# schematic.net
KiCad netlist of a schematic drawn in EAGLE
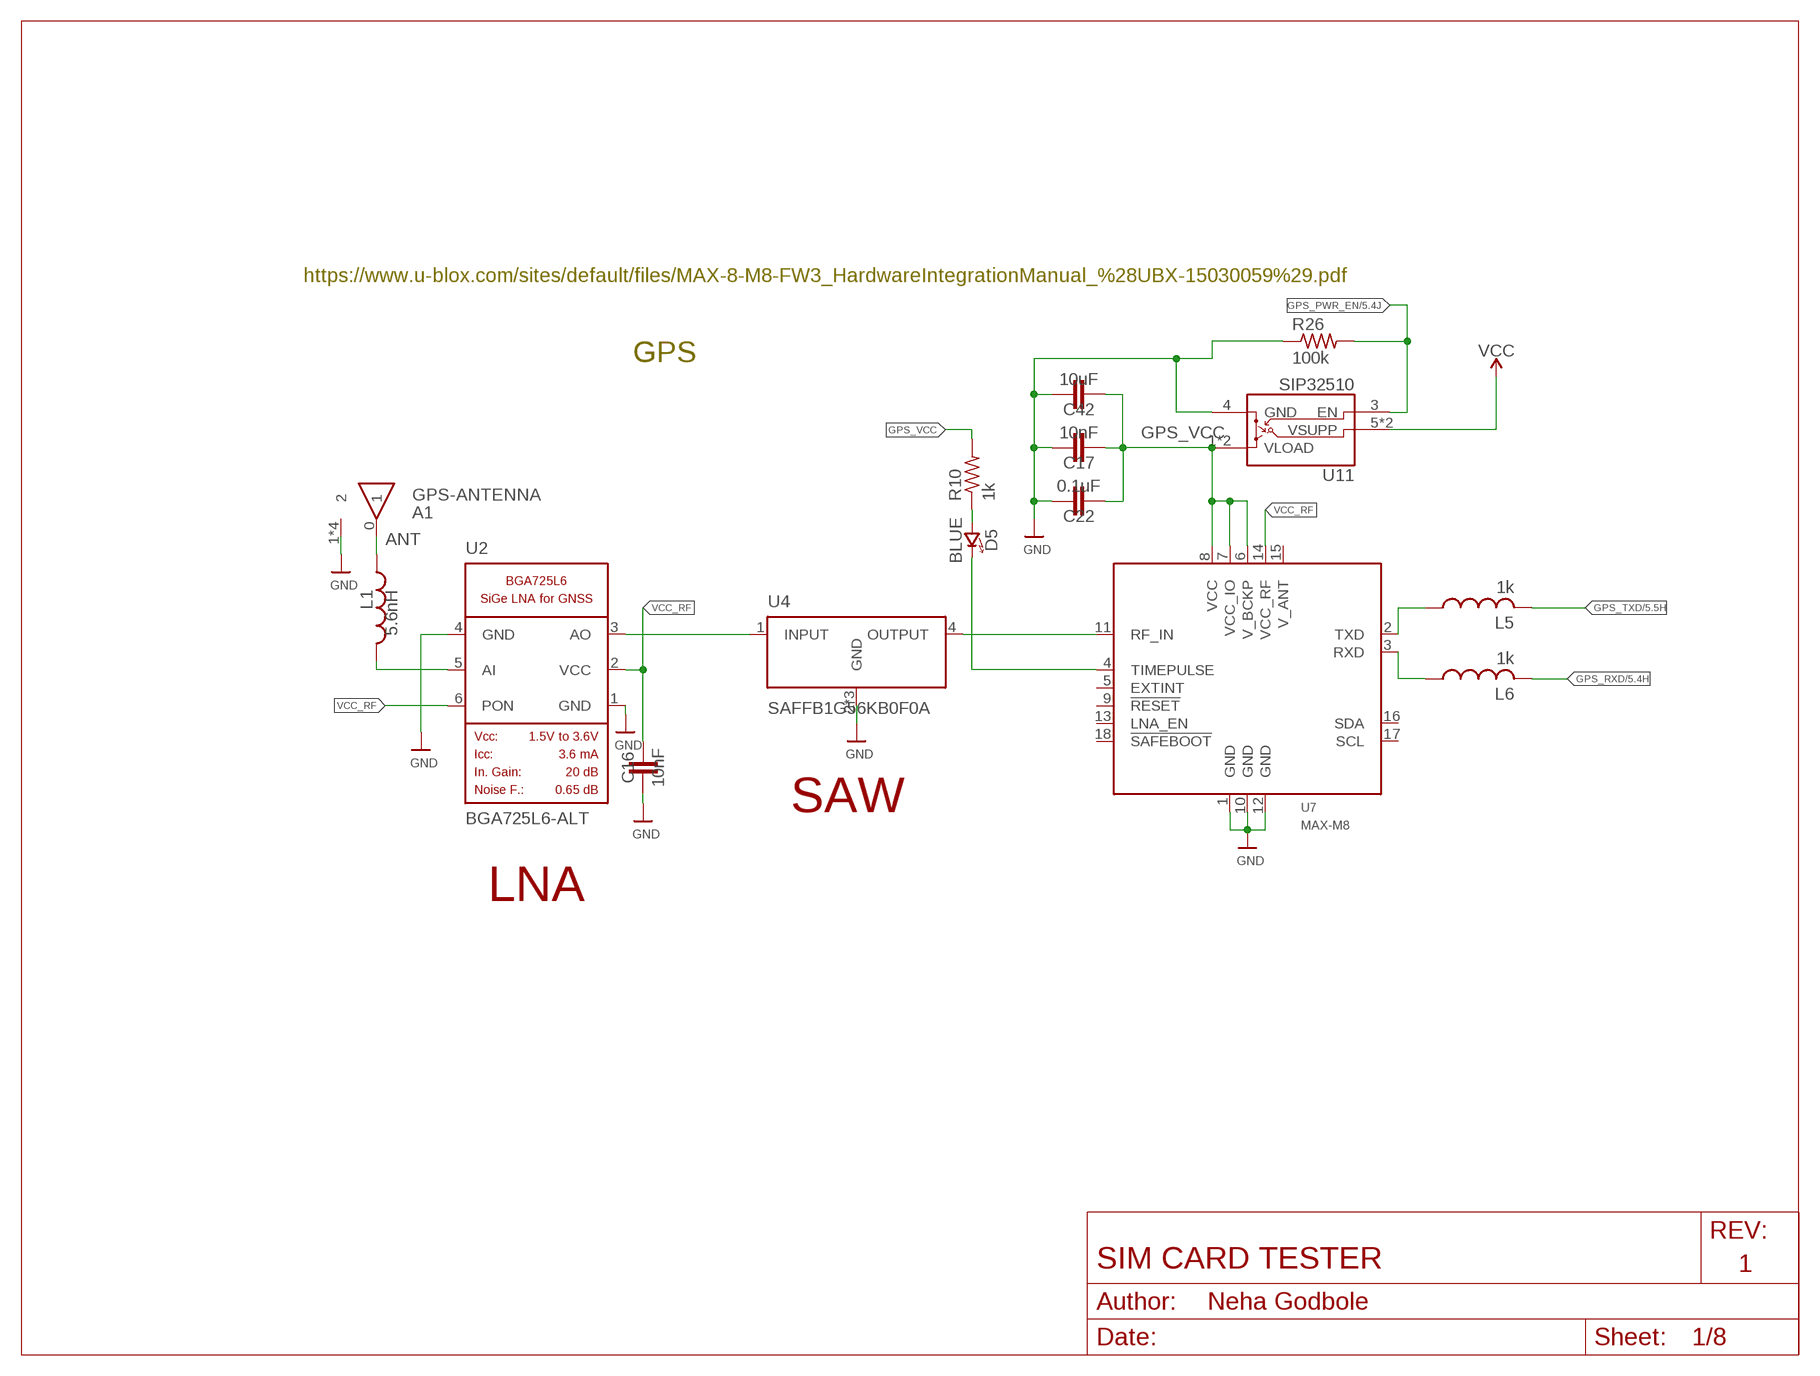
[diagram p0: schematic, sheet 1]
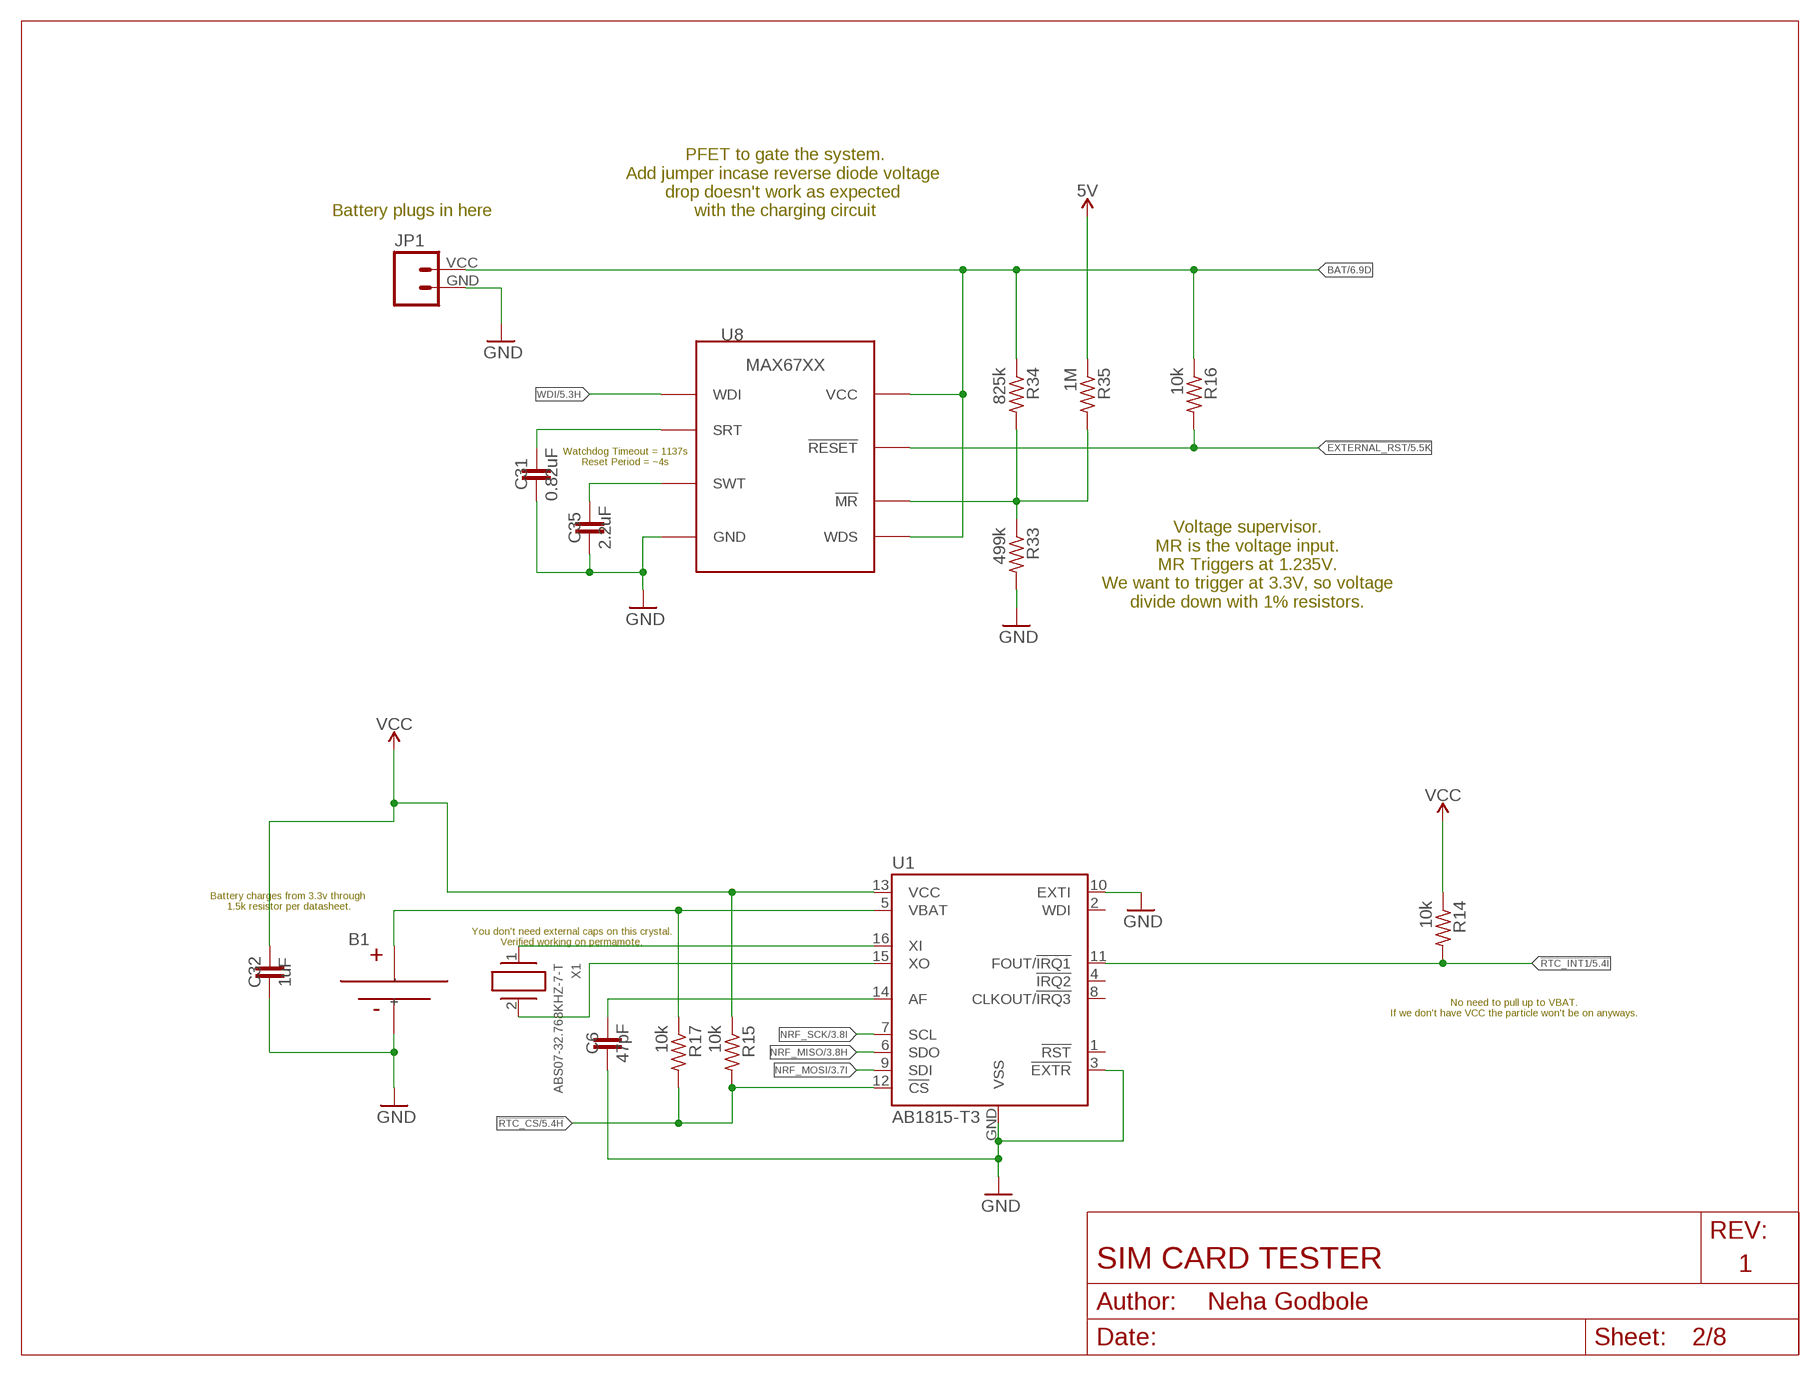
[diagram p1: schematic, sheet 2]
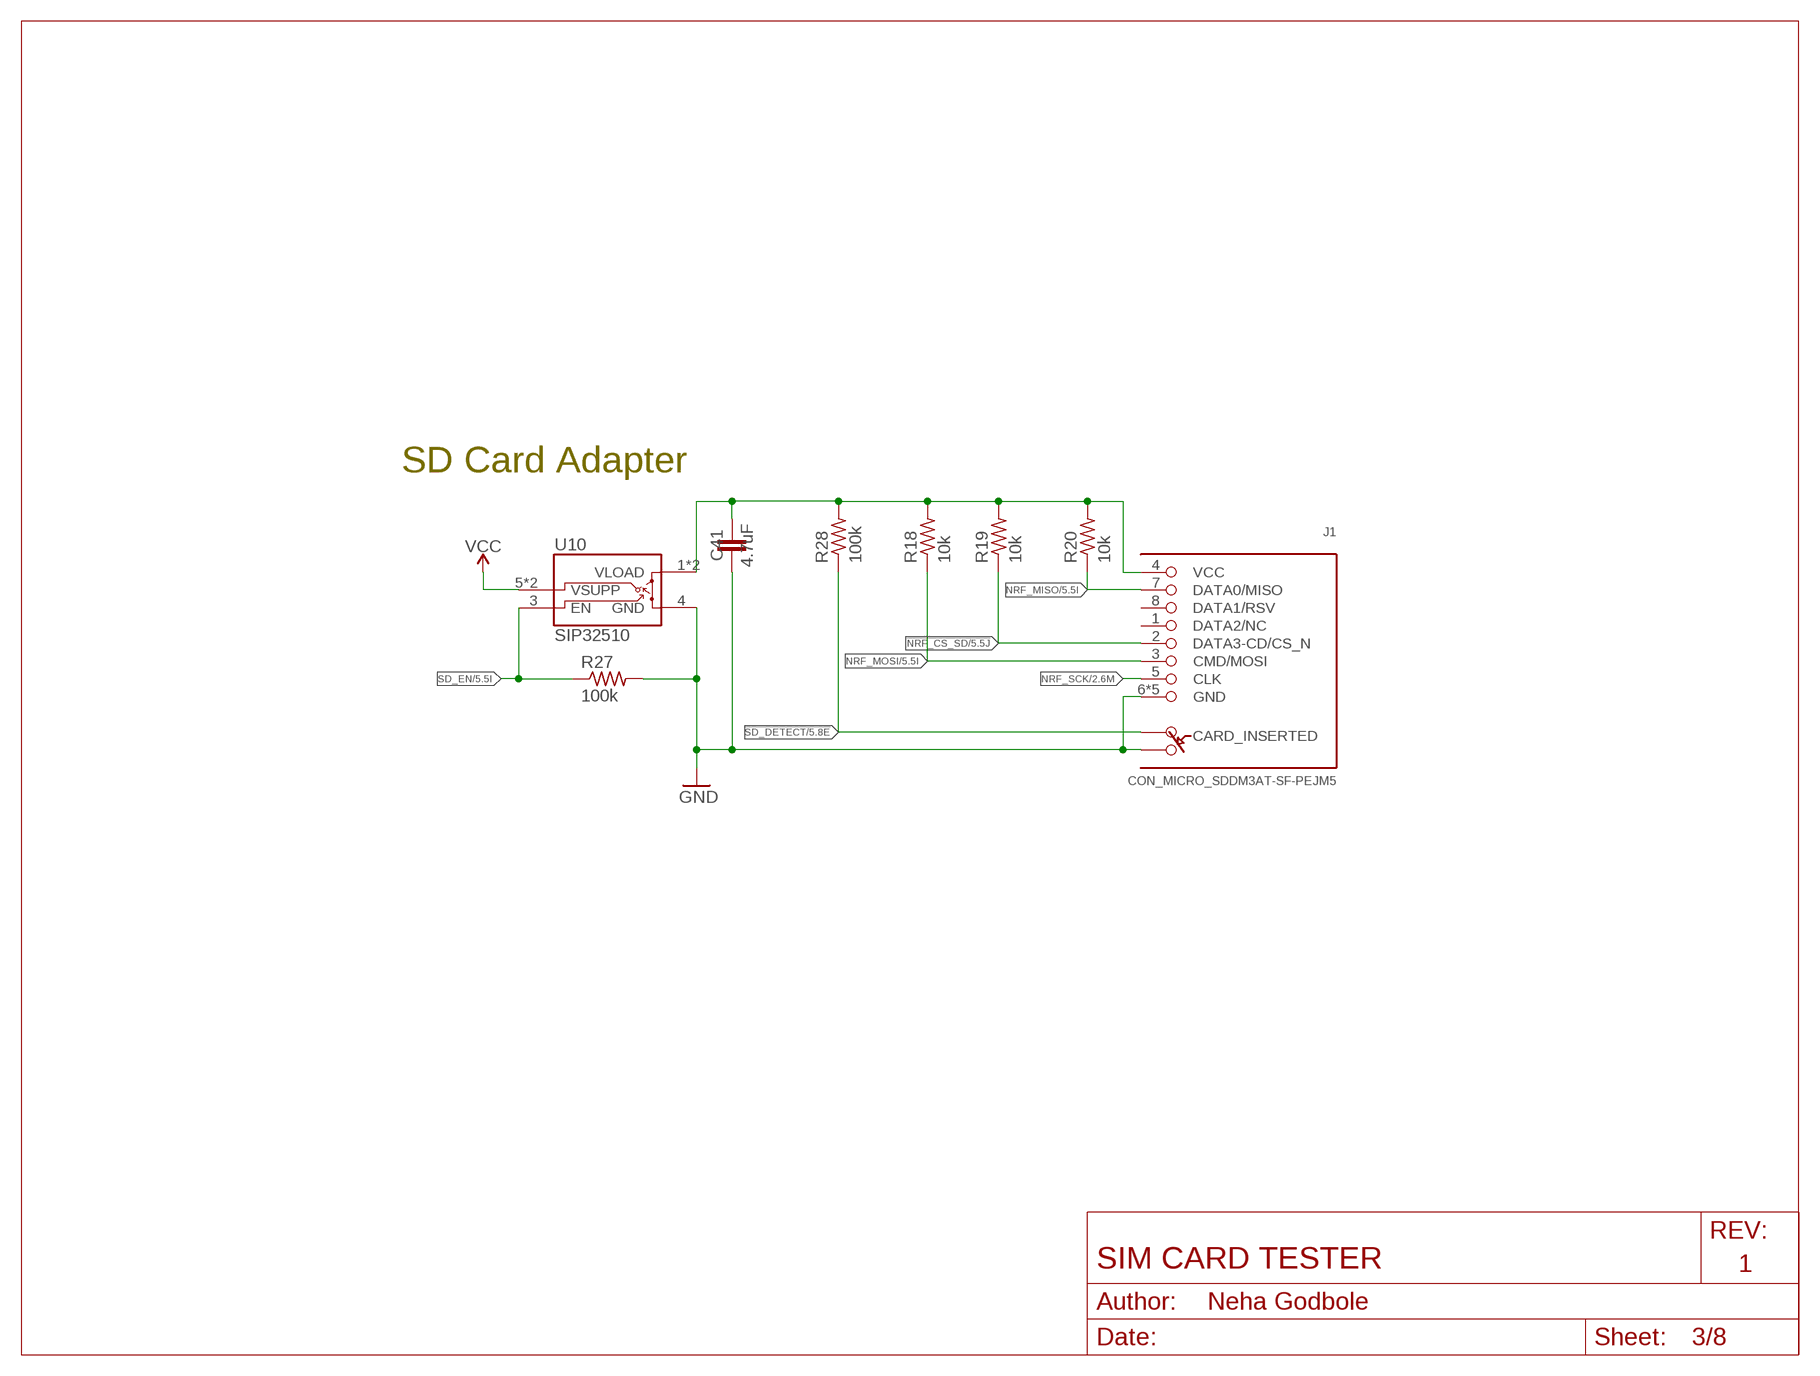
[diagram p2: schematic, sheet 3]
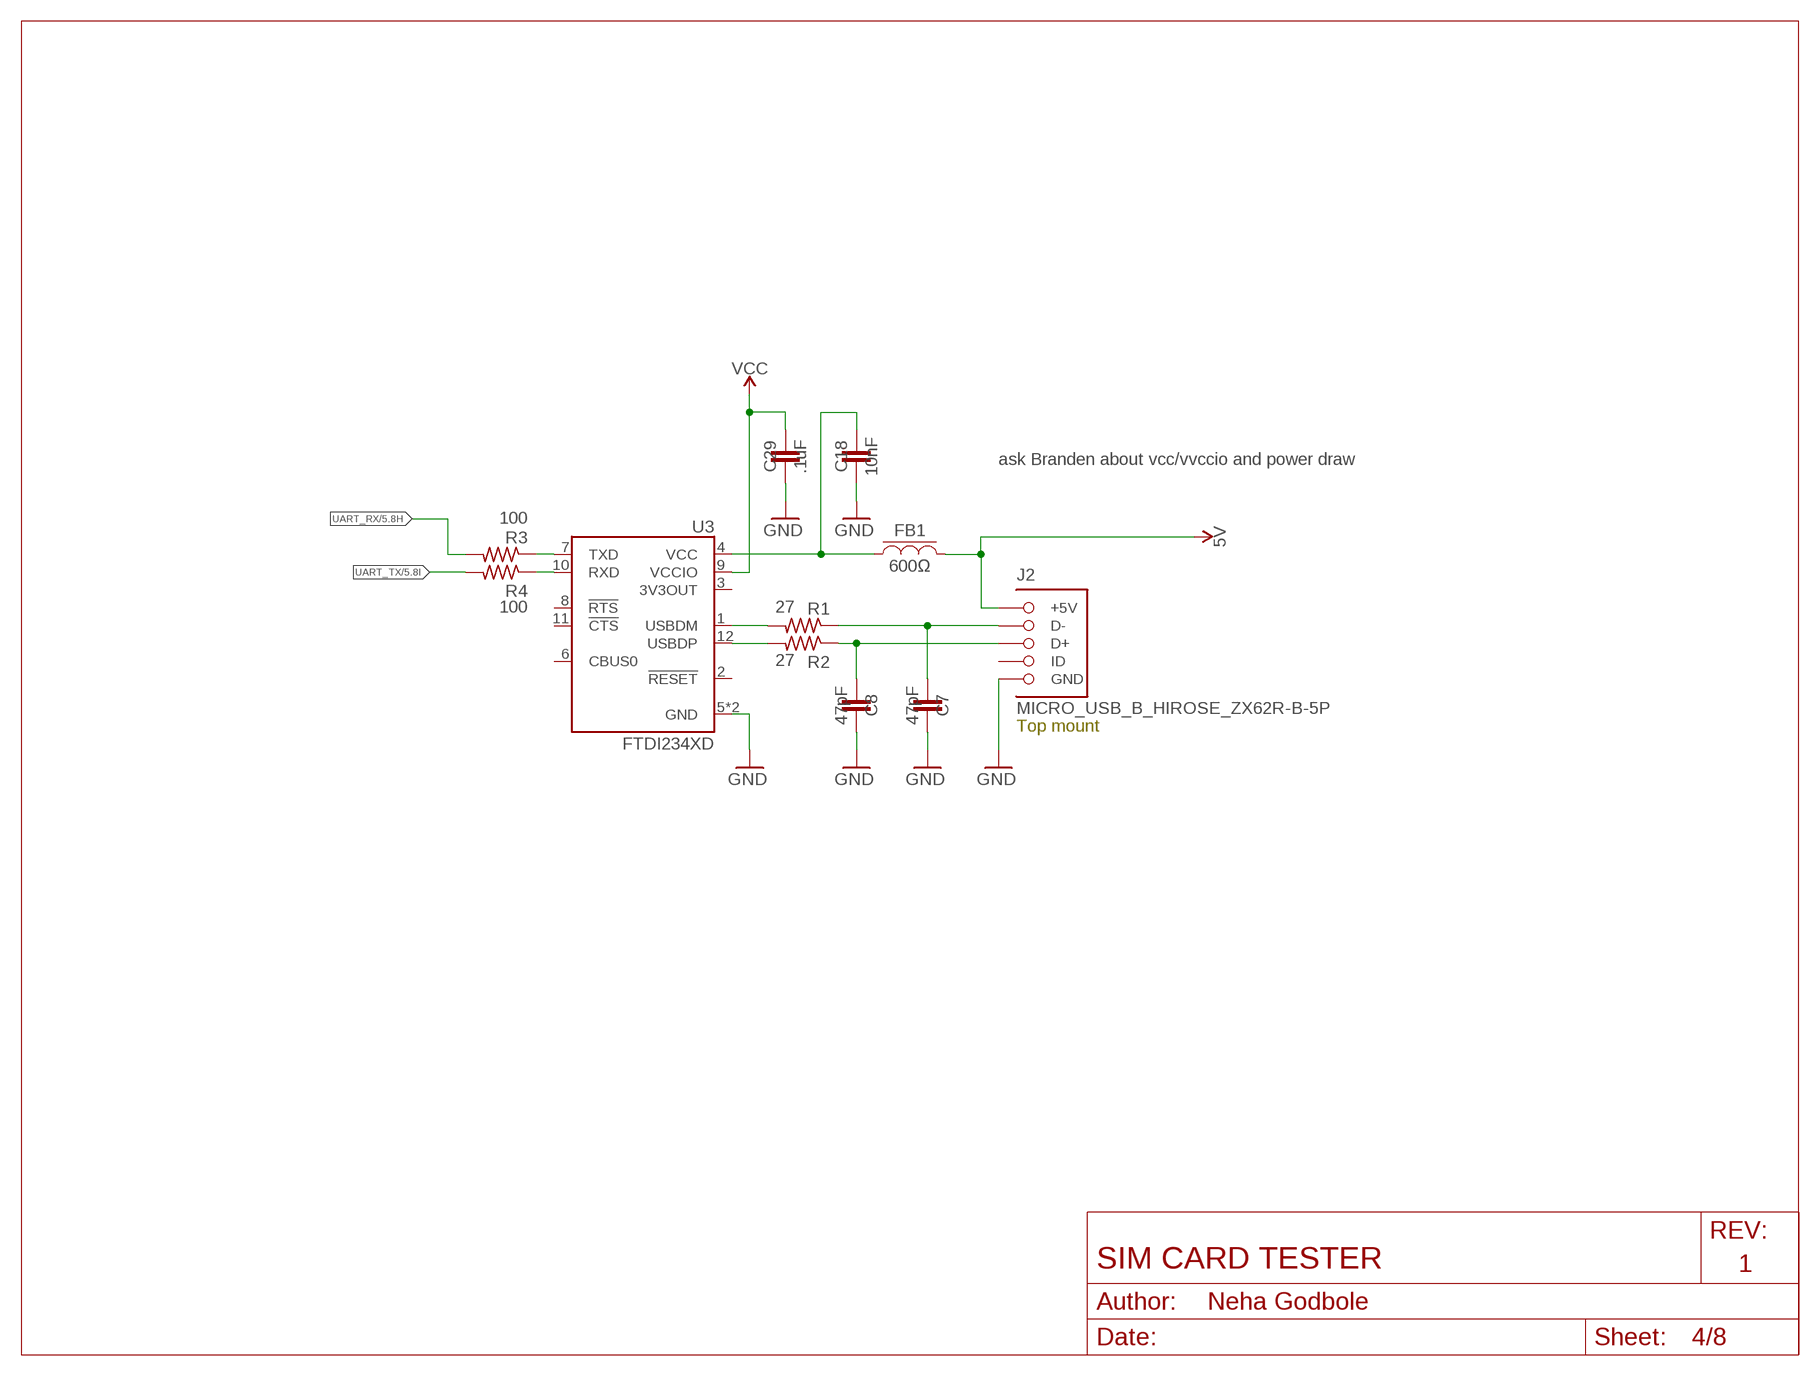
[diagram p3: schematic, sheet 4]
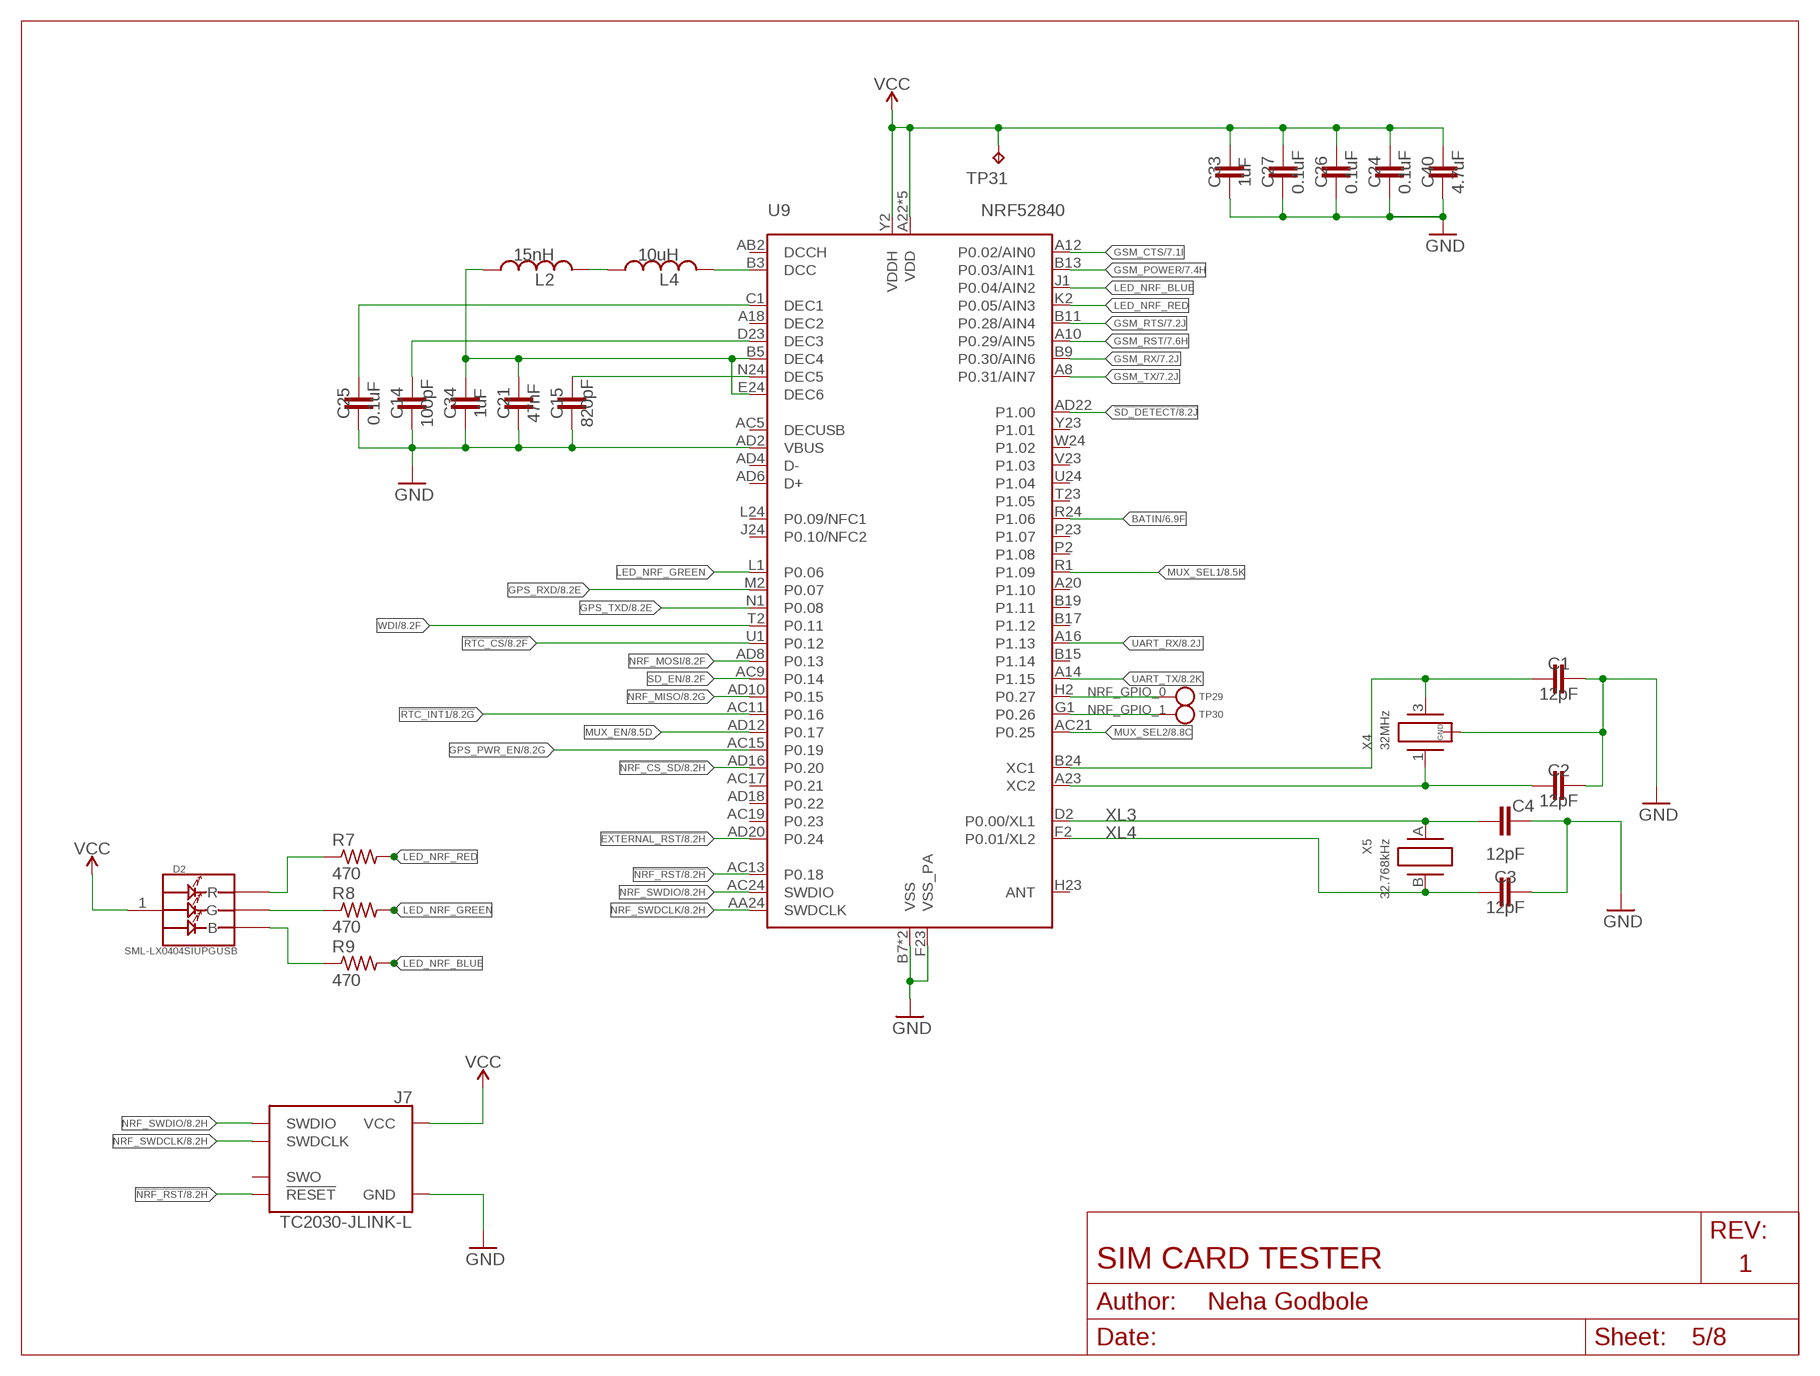
[diagram p4: schematic, sheet 5]
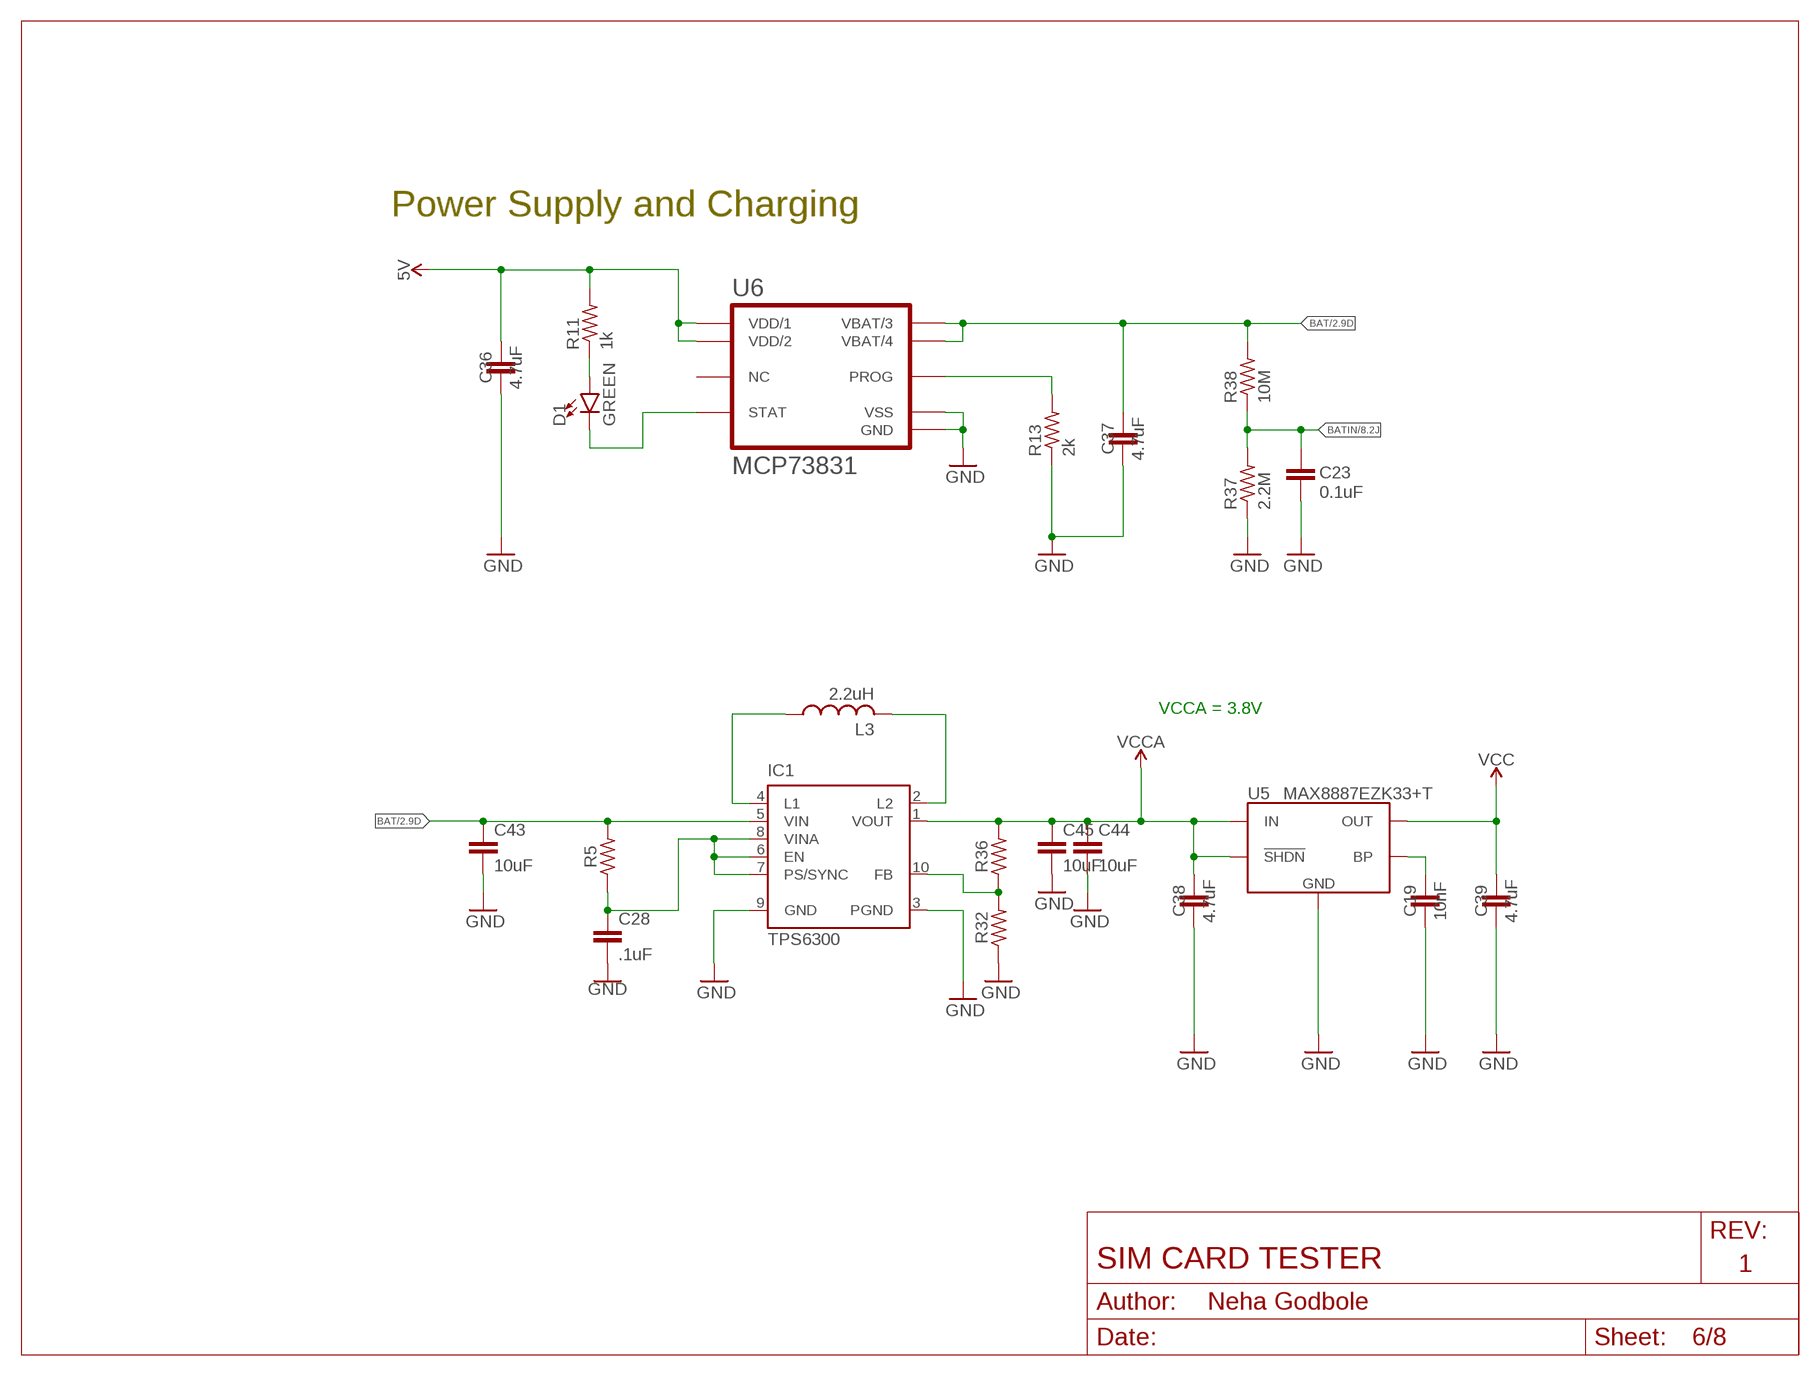
[diagram p5: schematic, sheet 6]
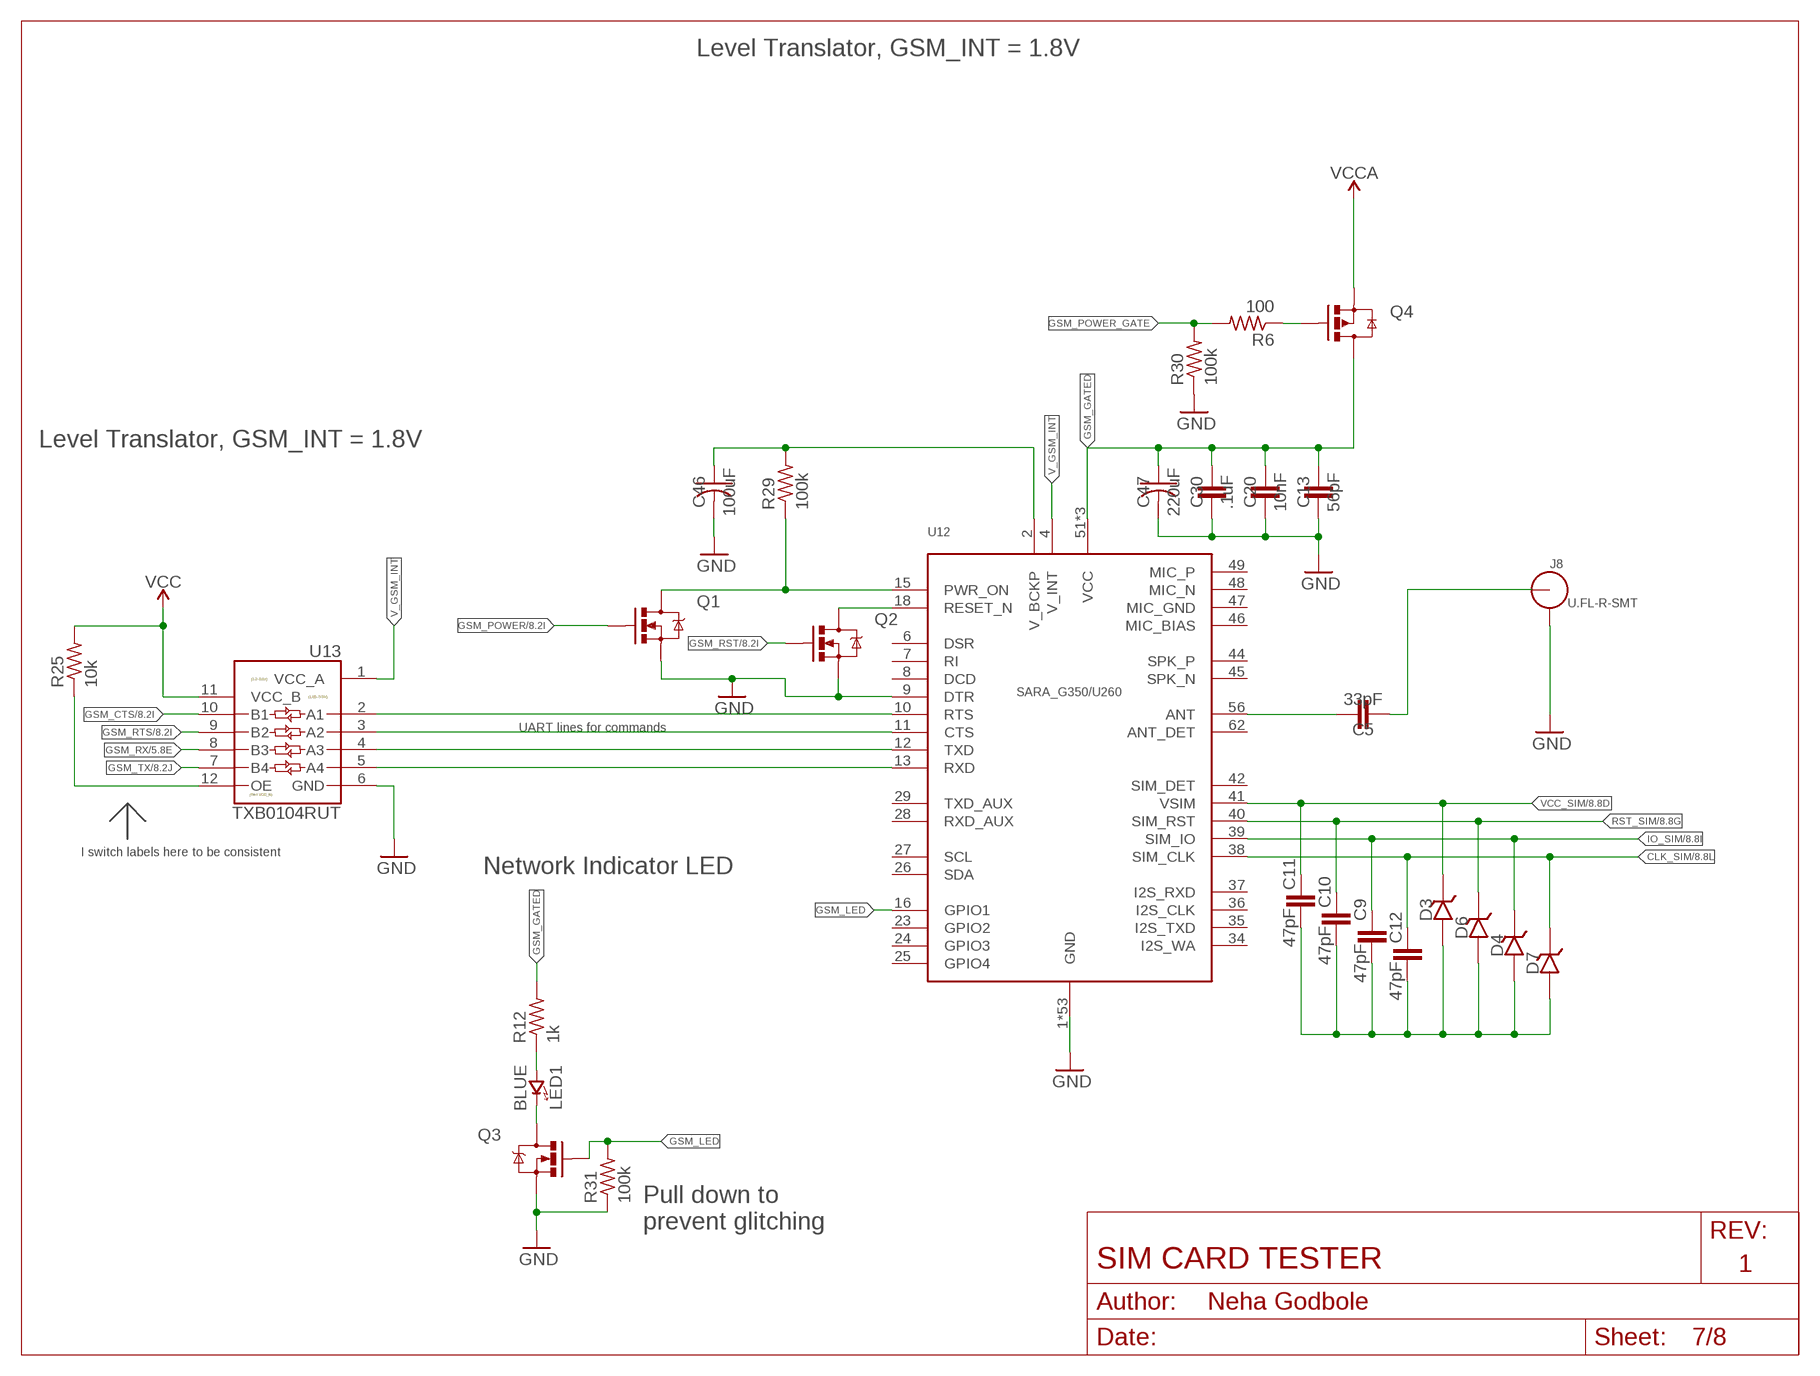
[diagram p6: schematic, sheet 7]
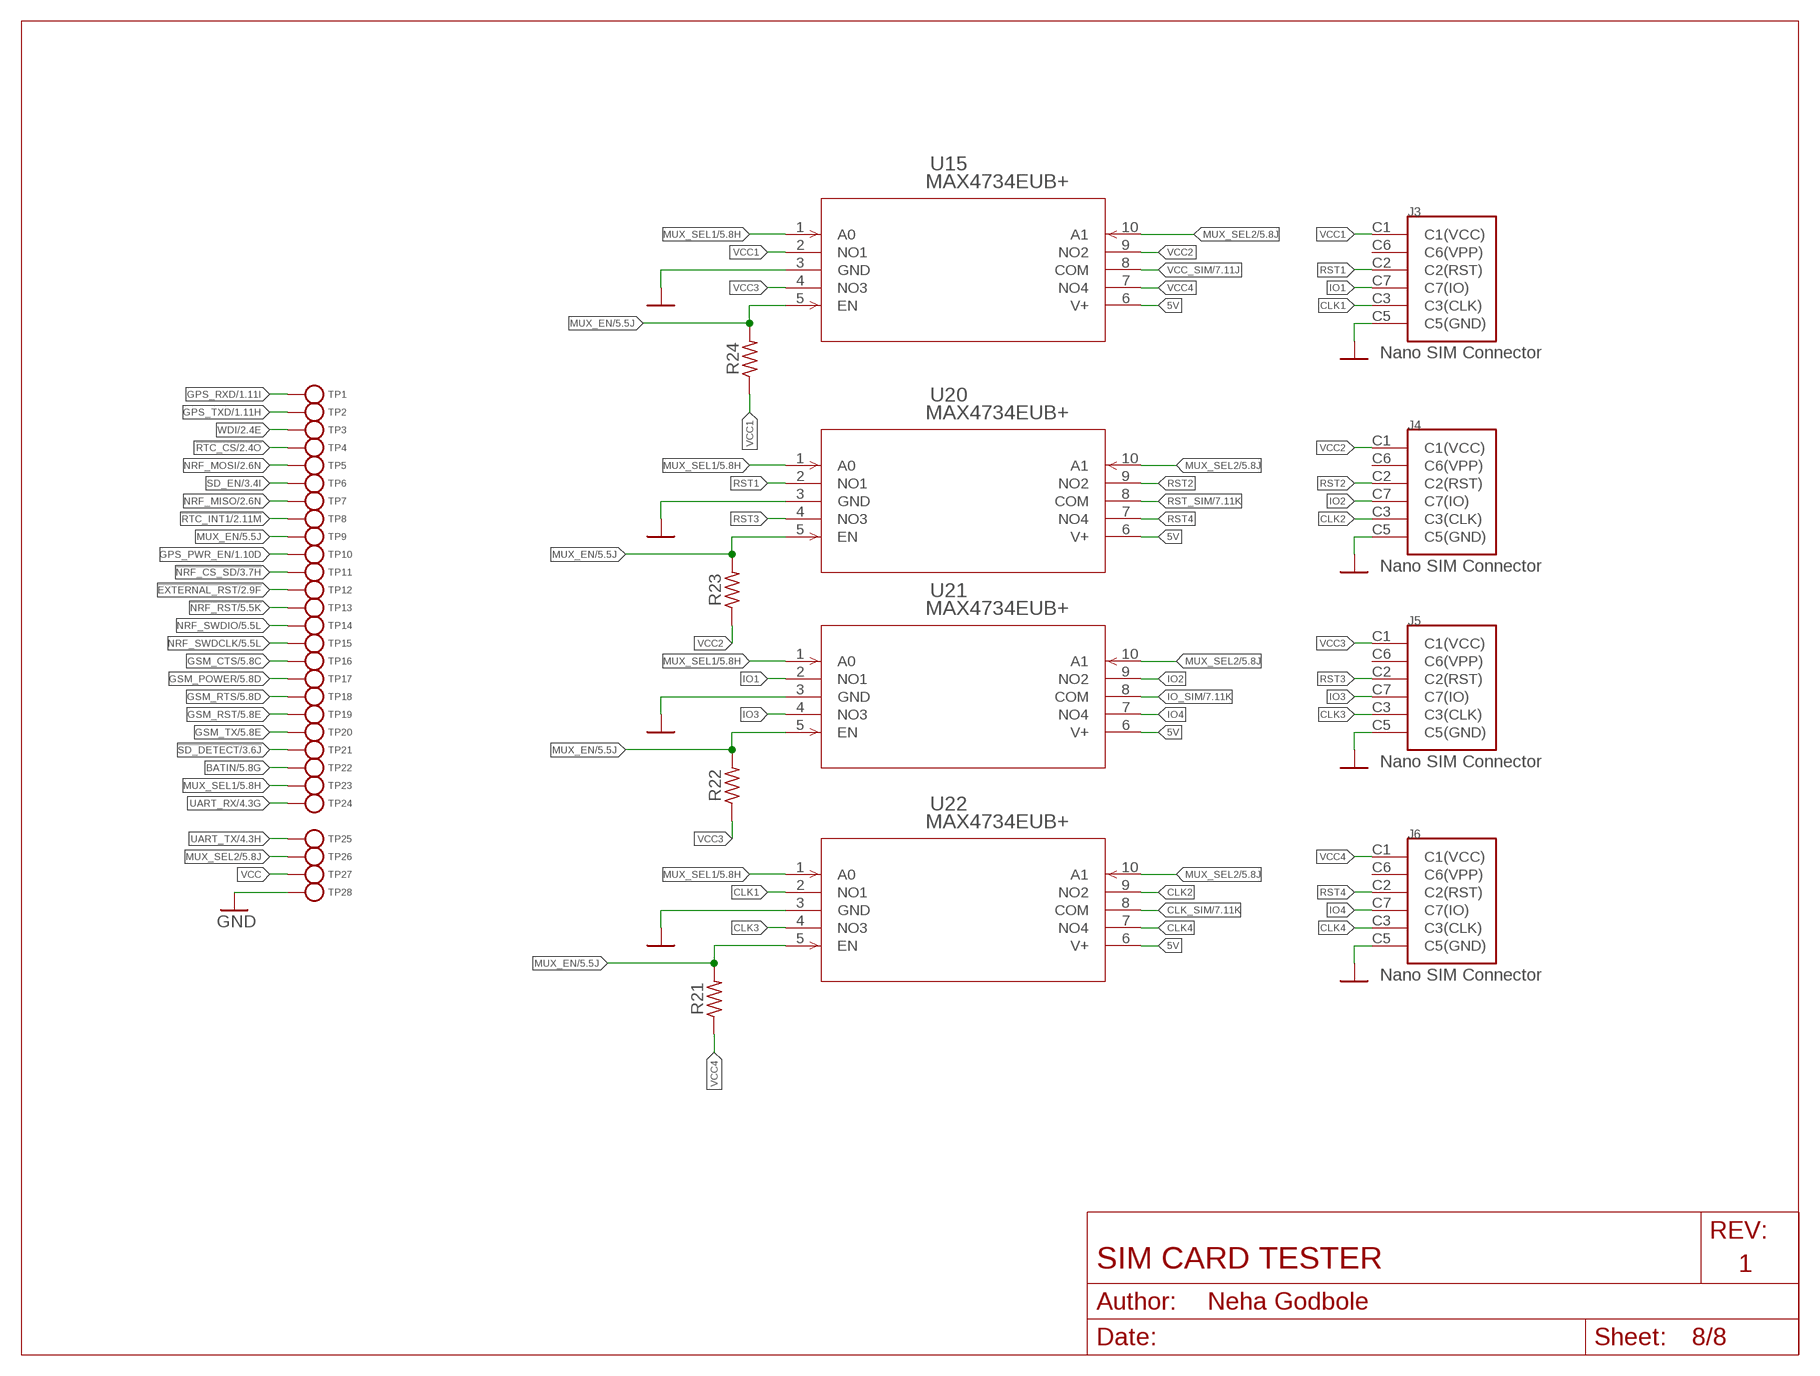
[diagram p7: schematic, sheet 8]

(export (version "E")
  (design (tool "Eeschema 10.0.6"))
  (components
    (comp (ref "A1")
      (value "GPS-ANTENNA")
      (footprint "eagle-import:ANT1818B00BT1516S")
      (description "PATCH ANT GPS/GLO CP SMD")
      (fields (field (name "MANUFACTURER") "Yageo") (field (name "MPN") "ANT1818B00BT1516S"))
      (libsource (lib "eagle-import") (part "GPS-ANTENNA"))
    )
    (comp (ref "C16")
      (value "10nF")
      (footprint "eagle-import:RESC0603_L")
      (fields
        (field (name "MANUFACTURER") "Murata Electronics")
        (field (name "MPN") "GRM033R61E103KA12D")
        (field (name "SPICEPREFIX") "C")
      )
      (libsource (lib "eagle-import") (part "CAPACITOR_0603_L"))
    )
    (comp (ref "C17")
      (value "10nF")
      (footprint "eagle-import:RESC0603_L")
      (fields (field (name "MANUFACTURER") "Murata Electronics") (field (name "MPN") "GRM033R61E103KA12D"))
      (libsource (lib "eagle-import") (part "CAPACITOR_0603_L"))
    )
    (comp (ref "C22")
      (value "0.1uF")
      (footprint "eagle-import:RESC0603_L")
      (fields (field (name "MANUFACTURER") "Murata Electronics") (field (name "MPN") "GRM033R61A104ME15D"))
      (libsource (lib "eagle-import") (part "CAPACITOR_0603_L"))
    )
    (comp (ref "C42")
      (value "10uF")
      (footprint "eagle-import:RESC0603_L")
      (fields (field (name "MANUFACTURER") "Murata Electronics") (field (name "MPN") "GRM188R60J106KE47D"))
      (libsource (lib "eagle-import") (part "CAPACITOR_0603_L"))
    )
    (comp (ref "D5")
      (value "BLUE")
      (footprint "eagle-import:LED-0603")
      (description "LED BLUE CLEAR SMD")
      (fields (field (name "MANUFACTURER") "Lite-On Inc.") (field (name "MPN") "LTST-C194TBKT"))
      (libsource (lib "eagle-import") (part "leds_LED0603"))
    )
    (comp (ref "L1")
      (value "5.6nH")
      (footprint "eagle-import:RESC0603_M")
      (fields (field (name "MANUFACTURER") "Murata Electronics") (field (name "MPN") "LQW18AN5N6G8ZD"))
      (libsource (lib "eagle-import") (part "INDUCTOR_0603_M"))
    )
    (comp (ref "L5")
      (value "1k")
      (footprint "eagle-import:RESC0603_M")
      (fields
        (field (name "DIGIKEY") "490-1015-1-ND")
        (field (name "MANUFACTURER") "BLM18AG102SN1D")
        (field (name "MPN") "Murata Electronics")
      )
      (libsource (lib "eagle-import") (part "INDUCTOR_0603_M"))
    )
    (comp (ref "L6")
      (value "1k")
      (footprint "eagle-import:RESC0603_M")
      (fields
        (field (name "DIGIKEY") "490-1015-1-ND")
        (field (name "MANUFACTURER") "BLM18AG102SN1D")
        (field (name "MPN") "Murata Electronics")
      )
      (libsource (lib "eagle-import") (part "INDUCTOR_0603_M"))
    )
    (comp (ref "R10")
      (value "1k")
      (footprint "eagle-import:R0603")
      (fields (field (name "MANUFACTURER") "Yageo") (field (name "MPN") "RC0603JR-071KL"))
      (libsource (lib "eagle-import") (part "R-US_R0603"))
    )
    (comp (ref "R26")
      (value "100k")
      (footprint "eagle-import:R0603")
      (fields (field (name "MANUFACTURER") "Yageo") (field (name "MPN") "RC0603JR-07100KL"))
      (libsource (lib "eagle-import") (part "R-US_R0603"))
    )
    (comp (ref "U2")
      (value "BGA725L6-ALT")
      (footprint "eagle-import:LNA-TSLP-6-2-ALT")
      (description "IC AMP MMIC RF LNA 20DB TSLP-6")
      (fields (field (name "MANUFACTURER") "Infineon") (field (name "MPN") "BGA725L6E6327FTSA1"))
      (libsource (lib "eagle-import") (part "BGA725L6-ALT"))
    )
    (comp (ref "U4")
      (value "SAFFB1G56KB0F0A")
      (footprint "eagle-import:QCS5I")
      (description "FILTER SAW 1.582GHZ 5SMD")
      (fields (field (name "MANUFACTURER") "Taiyo Yuden") (field (name "MPN") "F6QA1G582H2JM-J"))
      (libsource (lib "eagle-import") (part "FILTERS"))
    )
    (comp (ref "U7")
      (value "MAX-M8")
      (footprint "eagle-import:MAX-M8")
      (description "IC RECEIVER GPS/GNSS 18LCC")
      (fields (field (name "MANUFACTURER") "u-blox") (field (name "MPN") "MAX-M8Q-0"))
      (libsource (lib "eagle-import") (part "MAX-M8"))
    )
    (comp (ref "U11")
      (value "SIP32510")
      (footprint "eagle-import:TSOT23-6")
      (fields (field (name "MANUFACTURER") "Vishay") (field (name "MPN") "SIP32510DT-T1-GE3"))
      (libsource (lib "eagle-import") (part "SIP32510"))
    )
    (comp (ref "C1")
      (value "12pF")
      (footprint "eagle-import:RESC0603_L")
      (fields (field (name "MANUFACTURER") "Yageo") (field (name "MPN") "CC0603JRNPO9BN120"))
      (libsource (lib "eagle-import") (part "CAPACITOR_0603_L"))
    )
    (comp (ref "C2")
      (value "12pF")
      (footprint "eagle-import:RESC0603_L")
      (fields (field (name "MANUFACTURER") "Yageo") (field (name "MPN") "CC0603JRNPO9BN120"))
      (libsource (lib "eagle-import") (part "CAPACITOR_0603_L"))
    )
    (comp (ref "C3")
      (value "12pF")
      (footprint "eagle-import:RESC0603_L")
      (fields (field (name "MANUFACTURER") "Yageo") (field (name "MPN") "CC0603JRNPO9BN120"))
      (libsource (lib "eagle-import") (part "CAPACITOR_0603_L"))
    )
    (comp (ref "C4")
      (value "12pF")
      (footprint "eagle-import:RESC0603_L")
      (fields (field (name "MANUFACTURER") "Yageo") (field (name "MPN") "CC0603JRNPO9BN120"))
      (libsource (lib "eagle-import") (part "CAPACITOR_0603_L"))
    )
    (comp (ref "C14")
      (value "100pF")
      (footprint "eagle-import:RESC0603_L")
      (fields (field (name "MANUFACTURER") "Yageo") (field (name "MPN") "CC0603JRNPO9BN101"))
      (libsource (lib "eagle-import") (part "CAPACITOR_0603_L"))
    )
    (comp (ref "C15")
      (value "820pF")
      (footprint "eagle-import:RESC0603_L")
      (fields (field (name "MANUFACTURER") "Yageo") (field (name "MPN") "CC0603KRX7R9BB821"))
      (libsource (lib "eagle-import") (part "CAPACITOR_0603_L"))
    )
    (comp (ref "C21")
      (value "47nF")
      (footprint "eagle-import:RESC0603_L")
      (fields (field (name "MANUFACTURER") "Murata Electronics") (field (name "MPN") "GCJ188R71H473KA12D"))
      (libsource (lib "eagle-import") (part "CAPACITOR_0603_L"))
    )
    (comp (ref "C24")
      (value "0.1uF")
      (footprint "eagle-import:RESC0603_L")
      (fields (field (name "MANUFACTURER") "Murata Electronics") (field (name "MPN") "GRM033R61A104ME15D"))
      (libsource (lib "eagle-import") (part "CAPACITOR_0603_L"))
    )
    (comp (ref "C25")
      (value "0.1uF")
      (footprint "eagle-import:RESC0603_L")
      (fields (field (name "MANUFACTURER") "Murata Electronics") (field (name "MPN") "GRM033R61A104ME15D"))
      (libsource (lib "eagle-import") (part "CAPACITOR_0603_L"))
    )
    (comp (ref "C26")
      (value "0.1uF")
      (footprint "eagle-import:RESC0603_L")
      (fields (field (name "MANUFACTURER") "Murata Electronics") (field (name "MPN") "GRM033R61A104ME15D"))
      (libsource (lib "eagle-import") (part "CAPACITOR_0603_L"))
    )
    (comp (ref "C27")
      (value "0.1uF")
      (footprint "eagle-import:RESC0603_L")
      (fields (field (name "MANUFACTURER") "Murata Electronics") (field (name "MPN") "GRM033R61A104ME15D"))
      (libsource (lib "eagle-import") (part "CAPACITOR_0603_L"))
    )
    (comp (ref "C33")
      (value "1uF")
      (footprint "eagle-import:RESC0603_L")
      (fields (field (name "MANUFACTURER") "KEMET") (field (name "MPN") "C0603C105K8PACTU"))
      (libsource (lib "eagle-import") (part "CAPACITOR_0603_L"))
    )
    (comp (ref "C34")
      (value "1uF")
      (footprint "eagle-import:RESC0603_L")
      (fields (field (name "MANUFACTURER") "KEMET") (field (name "MPN") "C0603C105K8PACTU"))
      (libsource (lib "eagle-import") (part "CAPACITOR_0603_L"))
    )
    (comp (ref "C40")
      (value "4.7uF")
      (footprint "eagle-import:RESC0603_L")
      (fields (field (name "MANUFACTURER") "Murata Electronics") (field (name "MPN") "ZRB18AR6YA475KE05L"))
      (libsource (lib "eagle-import") (part "CAPACITOR_0603_L"))
    )
    (comp (ref "D2")
      (value "SML-LX0404SIUPGUSB")
      (footprint "eagle-import:1MM_SQ_4PAD")
      (fields (field (name "MANUFACTURER") "Lumex Opto"))
      (libsource (lib "eagle-import") (part "SML-LX0404SIUPGUSB"))
    )
    (comp (ref "J7")
      (value "TC2030-JLINK-L")
      (footprint "eagle-import:TC2030-IDC")
      (libsource (lib "eagle-import") (part "TC2030-JLINK-L"))
    )
    (comp (ref "L2")
      (value "15nH")
      (footprint "eagle-import:RESC0603_M")
      (fields (field (name "MANUFACTURER") "Murata Electronics") (field (name "MPN") "LQW18AN15NG8ZD"))
      (libsource (lib "eagle-import") (part "INDUCTOR_0603_M"))
    )
    (comp (ref "L4")
      (value "10uH")
      (footprint "eagle-import:RESC0603_M")
      (fields (field (name "MANUFACTURER") "Taiyo Yuden") (field (name "MPN") "CBMF1608T100K"))
      (libsource (lib "eagle-import") (part "INDUCTOR_0603_M"))
    )
    (comp (ref "R7")
      (value "470")
      (footprint "eagle-import:R0603")
      (fields
        (field (name "DIGIKEY") "311-470HRCT-ND")
        (field (name "MANUFACTURER") "Yageo")
        (field (name "MPN") "RC0603FR-07470RL")
      )
      (libsource (lib "eagle-import") (part "R-US_R0603"))
    )
    (comp (ref "R8")
      (value "470")
      (footprint "eagle-import:R0603")
      (fields
        (field (name "DIGIKEY") "311-470HRCT-ND")
        (field (name "MANUFACTURER") "Yageo")
        (field (name "MPN") "RC0603FR-07470RL")
      )
      (libsource (lib "eagle-import") (part "R-US_R0603"))
    )
    (comp (ref "R9")
      (value "470")
      (footprint "eagle-import:R0603")
      (fields
        (field (name "DIGIKEY") "311-470HRCT-ND")
        (field (name "MANUFACTURER") "Yageo")
        (field (name "MPN") "RC0603FR-07470RL")
      )
      (libsource (lib "eagle-import") (part "R-US_R0603"))
    )
    (comp (ref "TP29")
      (value "TEST-POINT")
      (footprint "eagle-import:PAD.03X.03")
      (libsource (lib "eagle-import") (part "TEST-POINT"))
    )
    (comp (ref "TP30")
      (value "TEST-POINT")
      (footprint "eagle-import:PAD.03X.03")
      (libsource (lib "eagle-import") (part "TEST-POINT"))
    )
    (comp (ref "TP31")
      (value "TPTP06SQ")
      (footprint "eagle-import:TP06SQ")
      (libsource (lib "eagle-import") (part "TPTP06SQ"))
    )
    (comp (ref "U9")
      (value "NRF52840")
      (footprint "eagle-import:AQFN73")
      (fields (field (name "MANUFACTURER") "NORIDIC SEMICONDUCTOR"))
      (libsource (lib "eagle-import") (part "NRF52840"))
    )
    (comp (ref "X4")
      (value "32MHz")
      (footprint "eagle-import:TXC-7V")
      (fields (field (name "MANUFACTURER") "TXC CORPORATION") (field (name "MPN") "7M-32.000MAHV-T"))
      (libsource (lib "eagle-import") (part "7V-32.000MAHV-T"))
    )
    (comp (ref "X5")
      (value "32.768kHz")
      (footprint "eagle-import:ABS05")
      (fields (field (name "MANUFACTURER") "Abracon") (field (name "MPN") "ABS05-32.768KHZ-9-T"))
      (libsource (lib "eagle-import") (part "ABS05-32.768KHZ-9-T"))
    )
    (comp (ref "J3")
      (value "NANO_SIM")
      (footprint "eagle-import:WURTH_NANO_SIM")
      (libsource (lib "eagle-import") (part "NANO_SIM"))
    )
    (comp (ref "J4")
      (value "NANO_SIM")
      (footprint "eagle-import:WURTH_NANO_SIM")
      (libsource (lib "eagle-import") (part "NANO_SIM"))
    )
    (comp (ref "J5")
      (value "NANO_SIM")
      (footprint "eagle-import:WURTH_NANO_SIM")
      (libsource (lib "eagle-import") (part "NANO_SIM"))
    )
    (comp (ref "J6")
      (value "NANO_SIM")
      (footprint "eagle-import:WURTH_NANO_SIM")
      (libsource (lib "eagle-import") (part "NANO_SIM"))
    )
    (comp (ref "R21")
      (value "10k")
      (footprint "eagle-import:R0603")
      (fields
        (field (name "DIGIKEY") "311-10KGRCT-ND")
        (field (name "MANUFACTURER") "Yageo")
        (field (name "MPN") "RC0603JR-0710KL")
      )
      (libsource (lib "eagle-import") (part "R-US_R0603"))
    )
    (comp (ref "R22")
      (value "10k")
      (footprint "eagle-import:R0603")
      (fields
        (field (name "DIGIKEY") "311-10KGRCT-ND")
        (field (name "MANUFACTURER") "Yageo")
        (field (name "MPN") "RC0603JR-0710KL")
      )
      (libsource (lib "eagle-import") (part "R-US_R0603"))
    )
    (comp (ref "R23")
      (value "10k")
      (footprint "eagle-import:R0603")
      (fields
        (field (name "DIGIKEY") "311-10KGRCT-ND")
        (field (name "MANUFACTURER") "Yageo")
        (field (name "MPN") "RC0603JR-0710KL")
      )
      (libsource (lib "eagle-import") (part "R-US_R0603"))
    )
    (comp (ref "R24")
      (value "10k")
      (footprint "eagle-import:R0603")
      (fields
        (field (name "DIGIKEY") "311-10KGRCT-ND")
        (field (name "MANUFACTURER") "Yageo")
        (field (name "MPN") "RC0603JR-0710KL")
      )
      (libsource (lib "eagle-import") (part "R-US_R0603"))
    )
    (comp (ref "TP1")
      (value "TEST-POINT")
      (footprint "eagle-import:PAD.03X.03")
      (libsource (lib "eagle-import") (part "TEST-POINT"))
    )
    (comp (ref "TP2")
      (value "TEST-POINT")
      (footprint "eagle-import:PAD.03X.03")
      (libsource (lib "eagle-import") (part "TEST-POINT"))
    )
    (comp (ref "TP3")
      (value "TEST-POINT")
      (footprint "eagle-import:PAD.03X.03")
      (libsource (lib "eagle-import") (part "TEST-POINT"))
    )
    (comp (ref "TP4")
      (value "TEST-POINT")
      (footprint "eagle-import:PAD.03X.03")
      (libsource (lib "eagle-import") (part "TEST-POINT"))
    )
    (comp (ref "TP5")
      (value "TEST-POINT")
      (footprint "eagle-import:PAD.03X.03")
      (libsource (lib "eagle-import") (part "TEST-POINT"))
    )
    (comp (ref "TP6")
      (value "TEST-POINT")
      (footprint "eagle-import:PAD.03X.03")
      (libsource (lib "eagle-import") (part "TEST-POINT"))
    )
    (comp (ref "TP7")
      (value "TEST-POINT")
      (footprint "eagle-import:PAD.03X.03")
      (libsource (lib "eagle-import") (part "TEST-POINT"))
    )
    (comp (ref "TP8")
      (value "TEST-POINT")
      (footprint "eagle-import:PAD.03X.03")
      (libsource (lib "eagle-import") (part "TEST-POINT"))
    )
    (comp (ref "TP9")
      (value "TEST-POINT")
      (footprint "eagle-import:PAD.03X.03")
      (libsource (lib "eagle-import") (part "TEST-POINT"))
    )
    (comp (ref "TP10")
      (value "TEST-POINT")
      (footprint "eagle-import:PAD.03X.03")
      (libsource (lib "eagle-import") (part "TEST-POINT"))
    )
    (comp (ref "TP11")
      (value "TEST-POINT")
      (footprint "eagle-import:PAD.03X.03")
      (libsource (lib "eagle-import") (part "TEST-POINT"))
    )
    (comp (ref "TP12")
      (value "TEST-POINT")
      (footprint "eagle-import:PAD.03X.03")
      (libsource (lib "eagle-import") (part "TEST-POINT"))
    )
    (comp (ref "TP13")
      (value "TEST-POINT")
      (footprint "eagle-import:PAD.03X.03")
      (libsource (lib "eagle-import") (part "TEST-POINT"))
    )
    (comp (ref "TP14")
      (value "TEST-POINT")
      (footprint "eagle-import:PAD.03X.03")
      (libsource (lib "eagle-import") (part "TEST-POINT"))
    )
    (comp (ref "TP15")
      (value "TEST-POINT")
      (footprint "eagle-import:PAD.03X.03")
      (libsource (lib "eagle-import") (part "TEST-POINT"))
    )
    (comp (ref "TP16")
      (value "TEST-POINT")
      (footprint "eagle-import:PAD.03X.03")
      (libsource (lib "eagle-import") (part "TEST-POINT"))
    )
    (comp (ref "TP17")
      (value "TEST-POINT")
      (footprint "eagle-import:PAD.03X.03")
      (libsource (lib "eagle-import") (part "TEST-POINT"))
    )
    (comp (ref "TP18")
      (value "TEST-POINT")
      (footprint "eagle-import:PAD.03X.03")
      (libsource (lib "eagle-import") (part "TEST-POINT"))
    )
    (comp (ref "TP19")
      (value "TEST-POINT")
      (footprint "eagle-import:PAD.03X.03")
      (libsource (lib "eagle-import") (part "TEST-POINT"))
    )
    (comp (ref "TP20")
      (value "TEST-POINT")
      (footprint "eagle-import:PAD.03X.03")
      (libsource (lib "eagle-import") (part "TEST-POINT"))
    )
    (comp (ref "TP21")
      (value "TEST-POINT")
      (footprint "eagle-import:PAD.03X.03")
      (libsource (lib "eagle-import") (part "TEST-POINT"))
    )
    (comp (ref "TP22")
      (value "TEST-POINT")
      (footprint "eagle-import:PAD.03X.03")
      (libsource (lib "eagle-import") (part "TEST-POINT"))
    )
    (comp (ref "TP23")
      (value "TEST-POINT")
      (footprint "eagle-import:PAD.03X.03")
      (libsource (lib "eagle-import") (part "TEST-POINT"))
    )
    (comp (ref "TP24")
      (value "TEST-POINT")
      (footprint "eagle-import:PAD.03X.03")
      (libsource (lib "eagle-import") (part "TEST-POINT"))
    )
    (comp (ref "TP25")
      (value "TEST-POINT")
      (footprint "eagle-import:PAD.03X.03")
      (libsource (lib "eagle-import") (part "TEST-POINT"))
    )
    (comp (ref "TP26")
      (value "TEST-POINT")
      (footprint "eagle-import:PAD.03X.03")
      (libsource (lib "eagle-import") (part "TEST-POINT"))
    )
    (comp (ref "TP27")
      (value "TEST-POINT")
      (footprint "eagle-import:PAD.03X.03")
      (libsource (lib "eagle-import") (part "TEST-POINT"))
    )
    (comp (ref "TP28")
      (value "TEST-POINT")
      (footprint "eagle-import:PAD.03X.03")
      (libsource (lib "eagle-import") (part "TEST-POINT"))
    )
    (comp (ref "U15")
      (value "MAX4734EUB+")
      (footprint "eagle-import:21-0061L")
      (libsource (lib "eagle-import") (part "MAX4734EUB+"))
    )
    (comp (ref "U20")
      (value "MAX4734EUB+")
      (footprint "eagle-import:21-0061L")
      (libsource (lib "eagle-import") (part "MAX4734EUB+"))
    )
    (comp (ref "U21")
      (value "MAX4734EUB+")
      (footprint "eagle-import:21-0061L")
      (libsource (lib "eagle-import") (part "MAX4734EUB+"))
    )
    (comp (ref "U22")
      (value "MAX4734EUB+")
      (footprint "eagle-import:21-0061L")
      (libsource (lib "eagle-import") (part "MAX4734EUB+"))
    )
    (comp (ref "C7")
      (value "47pF")
      (footprint "eagle-import:RESC0603_L")
      (fields (field (name "MANUFACTURER") "Yageo") (field (name "MPN") "CC0603JRNPO9BN470"))
      (libsource (lib "eagle-import") (part "CAPACITOR_0603_L"))
    )
    (comp (ref "C8")
      (value "47pF")
      (footprint "eagle-import:RESC0603_L")
      (fields (field (name "MANUFACTURER") "Yageo") (field (name "MPN") "CC0603JRNPO9BN470"))
      (libsource (lib "eagle-import") (part "CAPACITOR_0603_L"))
    )
    (comp (ref "C18")
      (value "10nF")
      (footprint "eagle-import:RESC0603_L")
      (fields (field (name "MANUFACTURER") "Murata Electronics") (field (name "MPN") "GRM033R61E103KA12D"))
      (libsource (lib "eagle-import") (part "CAPACITOR_0603_L"))
    )
    (comp (ref "C29")
      (value ".1uF")
      (footprint "eagle-import:RESC0603_L")
      (fields (field (name "MANUFACTURER") "Murata Electronics") (field (name "MPN") "GRM033R61A104ME15D"))
      (libsource (lib "eagle-import") (part "CAPACITOR_0603_L"))
    )
    (comp (ref "FB1")
      (value "600Ω")
      (footprint "eagle-import:0805_CAP")
      (libsource (lib "eagle-import") (part "FERRITE_BEAD0805"))
    )
    (comp (ref "J2")
      (value "MICRO_USB_B_HIROSE_ZX62R-B-5P")
      (footprint "eagle-import:USB_MICRO_B-HIROSE-ZX62R-B-5P")
      (fields (field (name "DIGIKEY") "H125274CT-ND"))
      (libsource (lib "eagle-import") (part "MICRO_USB_B_HIROSE_ZX62R-B-5P"))
    )
    (comp (ref "R1")
      (value "27")
      (footprint "eagle-import:R0603")
      (fields (field (name "MANUFACTURER") "Yageo") (field (name "MPN") "RC0603JR-0727RL"))
      (libsource (lib "eagle-import") (part "R-US_R0603"))
    )
    (comp (ref "R2")
      (value "27")
      (footprint "eagle-import:R0603")
      (fields (field (name "MANUFACTURER") "Yageo") (field (name "MPN") "RC0603JR-0727RL"))
      (libsource (lib "eagle-import") (part "R-US_R0603"))
    )
    (comp (ref "R3")
      (value "100")
      (footprint "eagle-import:R0603")
      (fields (field (name "MANUFACTURER") "Yageo") (field (name "MPN") "RC0603FR-07100RL"))
      (libsource (lib "eagle-import") (part "R-US_R0603"))
    )
    (comp (ref "R4")
      (value "100")
      (footprint "eagle-import:R0603")
      (fields (field (name "MANUFACTURER") "Yageo") (field (name "MPN") "RC0603FR-07100RL"))
      (libsource (lib "eagle-import") (part "R-US_R0603"))
    )
    (comp (ref "U3")
      (value "FTDI234XD")
      (footprint "eagle-import:DFN-12_3MM")
      (libsource (lib "eagle-import") (part "FTDI234XD"))
    )
    (comp (ref "C41")
      (value "4.7uF")
      (footprint "eagle-import:RESC0603_L")
      (fields (field (name "MANUFACTURER") "Murata Electronics") (field (name "MPN") "ZRB18AR6YA475KE05L"))
      (libsource (lib "eagle-import") (part "CAPACITOR_0603_L"))
    )
    (comp (ref "J1")
      (value "CON_MICRO_SDDM3AT-SF-PEJM5")
      (footprint "eagle-import:DM3AT-SF-PEJM5")
      (fields (field (name "MPN") "DM3AT-SF-PEJM5"))
      (libsource (lib "eagle-import") (part "CON_MICRO_SDDM3AT-SF-PEJM5"))
    )
    (comp (ref "R18")
      (value "10k")
      (footprint "eagle-import:R0603")
      (fields
        (field (name "DIGIKEY") "311-10KGRCT-ND")
        (field (name "MANUFACTURER") "Yageo")
        (field (name "MPN") "RC0603JR-0710KL")
      )
      (libsource (lib "eagle-import") (part "R-US_R0603"))
    )
    (comp (ref "R19")
      (value "10k")
      (footprint "eagle-import:R0603")
      (fields
        (field (name "DIGIKEY") "311-10KGRCT-ND")
        (field (name "MANUFACTURER") "Yageo")
        (field (name "MPN") "RC0603JR-0710KL")
      )
      (libsource (lib "eagle-import") (part "R-US_R0603"))
    )
    (comp (ref "R20")
      (value "10k")
      (footprint "eagle-import:R0603")
      (fields
        (field (name "DIGIKEY") "311-10KGRCT-ND")
        (field (name "MANUFACTURER") "Yageo")
        (field (name "MPN") "RC0603JR-0710KL")
      )
      (libsource (lib "eagle-import") (part "R-US_R0603"))
    )
    (comp (ref "R27")
      (value "100k")
      (footprint "eagle-import:R0603")
      (fields
        (field (name "DIGIKEY") "311-100KGRCT-ND")
        (field (name "MANUFACTURER") "Yageo")
        (field (name "MPN") "RC0603JR-07100KL")
      )
      (libsource (lib "eagle-import") (part "R-US_R0603"))
    )
    (comp (ref "R28")
      (value "100k")
      (footprint "eagle-import:R0603")
      (fields
        (field (name "DIGIKEY") "311-100KGRCT-ND")
        (field (name "MANUFACTURER") "Yageo")
        (field (name "MPN") "RC0603JR-07100KL")
      )
      (libsource (lib "eagle-import") (part "R-US_R0603"))
    )
    (comp (ref "U10")
      (value "SIP32510")
      (footprint "eagle-import:TSOT23-6")
      (fields (field (name "MANUFACTURER") "Vishay") (field (name "MPN") "SIP32510DT-T1-GE3"))
      (libsource (lib "eagle-import") (part "SIP32510"))
    )
    (comp (ref "B1")
      (value "MS518SE")
      (footprint "eagle-import:MS518SE-FL35E")
      (fields (field (name "MANUFACTURER") "Seiko") (field (name "MPN") "MS518SE-FL35E"))
      (libsource (lib "eagle-import") (part "MS518SE"))
    )
    (comp (ref "C6")
      (value "47pF")
      (footprint "eagle-import:RESC0603_L")
      (fields (field (name "MANUFACTURER") "KEMET") (field (name "MPN") "C0603C105K8PACTU"))
      (libsource (lib "eagle-import") (part "CAPACITOR_0603_L"))
    )
    (comp (ref "C31")
      (value "0.82uF")
      (footprint "eagle-import:RESC0603_L")
      (fields (field (name "MANUFACTURER") "KEMET") (field (name "MPN") "C0603C824K8PACTU"))
      (libsource (lib "eagle-import") (part "CAPACITOR_0603_L"))
    )
    (comp (ref "C32")
      (value "1uF")
      (footprint "eagle-import:RESC0603_L")
      (fields (field (name "MANUFACTURER") "KEMET") (field (name "MPN") "C0603C105K8PACTU"))
      (libsource (lib "eagle-import") (part "CAPACITOR_0603_L"))
    )
    (comp (ref "C35")
      (value "2.2uF")
      (footprint "eagle-import:RESC0603_L")
      (fields (field (name "MANUFACTURER") "Murata Electronics") (field (name "MPN") "GRM188R61E225MA12D"))
      (libsource (lib "eagle-import") (part "CAPACITOR_0603_L"))
    )
    (comp (ref "JP1")
      (value "M024UCON-15767")
      (footprint "eagle-import:JST-2-SMD-VERT")
      (description "CONN HEADER PH TOP 2POS 2MM SMD")
      (fields
        (field (name "MANUFACTURER") "JST Sales America Inc.")
        (field (name "MPN") "B2B-PH-SM4-TB(LF)(SN)")
      )
      (libsource (lib "eagle-import") (part "M024UCON-15767"))
    )
    (comp (ref "R14")
      (value "10k")
      (footprint "eagle-import:R0603")
      (fields (field (name "MANUFACTURER") "Yageo") (field (name "MPN") "RC0603JR-0710KL"))
      (libsource (lib "eagle-import") (part "R-US_R0603"))
    )
    (comp (ref "R15")
      (value "10k")
      (footprint "eagle-import:R0603")
      (fields (field (name "MANUFACTURER") "Yageo") (field (name "MPN") "RC0603JR-0710KL"))
      (libsource (lib "eagle-import") (part "R-US_R0603"))
    )
    (comp (ref "R16")
      (value "10k")
      (footprint "eagle-import:R0603")
      (fields (field (name "MANUFACTURER") "Yageo") (field (name "MPN") "RC0603JR-0710KL"))
      (libsource (lib "eagle-import") (part "R-US_R0603"))
    )
    (comp (ref "R17")
      (value "10k")
      (footprint "eagle-import:R0603")
      (fields (field (name "MANUFACTURER") "Yageo") (field (name "MPN") "RC0603JR-0710KL"))
      (libsource (lib "eagle-import") (part "R-US_R0603"))
    )
    (comp (ref "R33")
      (value "499k")
      (footprint "eagle-import:R0603")
      (fields (field (name "MANUFACTURER") "Yageo") (field (name "MPN") "RC0603FR-07499KL"))
      (libsource (lib "eagle-import") (part "R-US_R0603"))
    )
    (comp (ref "R34")
      (value "825k")
      (footprint "eagle-import:R0603")
      (fields (field (name "MANUFACTURER") "Yageo") (field (name "MPN") "RC0603FR-07825KL"))
      (libsource (lib "eagle-import") (part "R-US_R0603"))
    )
    (comp (ref "R35")
      (value "1M")
      (footprint "eagle-import:R0603")
      (fields (field (name "MANUFACTURER") "Yageo") (field (name "MPN") "RC0603FR-071ML"))
      (libsource (lib "eagle-import") (part "R-US_R0603"))
    )
    (comp (ref "U1")
      (value "AB1815-T3")
      (footprint "eagle-import:QFN-16-3MM")
      (fields (field (name "MANUFACTURER") "Abracon"))
      (libsource (lib "eagle-import") (part "AB1815-T3"))
    )
    (comp (ref "U8")
      (value "MAX67XXMAX6749MAX67XX")
      (footprint "eagle-import:SOT-23-8")
      (fields (field (name "MANUFACTURER") "Maxim Integrated") (field (name "MPN") "MAX6749KA+T"))
      (libsource (lib "eagle-import") (part "MAX67XXMAX67XXMAX6749"))
    )
    (comp (ref "X1")
      (value "ABS07-32.768KHZ-7-T")
      (footprint "eagle-import:2-SMD")
      (fields (field (name "MANUFACTURER") "ABRACON") (field (name "MPN") "ABS07-32.768KHZ-7-T "))
      (libsource (lib "eagle-import") (part "ABS07-32.768KHZ-7-T"))
    )
    (comp (ref "C5")
      (value "33pF")
      (footprint "eagle-import:RESC0603_L")
      (fields (field (name "MANUFACTURER") "KEMET") (field (name "MPN") "C0603C330J1GACTU"))
      (libsource (lib "eagle-import") (part "CAPACITOR_0603_L"))
    )
    (comp (ref "C9")
      (value "47pF")
      (footprint "eagle-import:RESC0603_L")
      (fields (field (name "MANUFACTURER") "Yageo") (field (name "MPN") "CC0603JRNPO9BN470"))
      (libsource (lib "eagle-import") (part "CAPACITOR_0603_L"))
    )
    (comp (ref "C10")
      (value "47pF")
      (footprint "eagle-import:RESC0603_L")
      (fields (field (name "MANUFACTURER") "Yageo") (field (name "MPN") "CC0603JRNPO9BN470"))
      (libsource (lib "eagle-import") (part "CAPACITOR_0603_L"))
    )
    (comp (ref "C11")
      (value "47pF")
      (footprint "eagle-import:RESC0603_L")
      (fields (field (name "MANUFACTURER") "Yageo") (field (name "MPN") "CC0603JRNPO9BN470"))
      (libsource (lib "eagle-import") (part "CAPACITOR_0603_L"))
    )
    (comp (ref "C12")
      (value "47pF")
      (footprint "eagle-import:RESC0603_L")
      (fields (field (name "MANUFACTURER") "Yageo") (field (name "MPN") "CC0603JRNPO9BN470"))
      (libsource (lib "eagle-import") (part "CAPACITOR_0603_L"))
    )
    (comp (ref "C13")
      (value "56pF")
      (footprint "eagle-import:RESC0603_L")
      (fields (field (name "MANUFACTURER") "Yageo") (field (name "MPN") "CC0603JRNPO9BN560"))
      (libsource (lib "eagle-import") (part "CAPACITOR_0603_L"))
    )
    (comp (ref "C20")
      (value "10nF")
      (footprint "eagle-import:RESC0603_L")
      (fields (field (name "MANUFACTURER") "Murata Electronics") (field (name "MPN") "GRM033R61E103KA12D"))
      (libsource (lib "eagle-import") (part "CAPACITOR_0603_L"))
    )
    (comp (ref "C30")
      (value ".1uF")
      (footprint "eagle-import:RESC0603_L")
      (fields (field (name "MANUFACTURER") "Murata Electronics") (field (name "MPN") "GRM033R61A104ME15D"))
      (libsource (lib "eagle-import") (part "CAPACITOR_0603_L"))
    )
    (comp (ref "C46")
      (value "100uF")
      (footprint "eagle-import:C1210")
      (fields (field (name "MANUFACTURER") "Murata Electronics") (field (name "MPN") "GRM32ER61A107ME20L"))
      (libsource (lib "eagle-import") (part "C-USC1210"))
    )
    (comp (ref "C47")
      (value "220uF")
      (footprint "eagle-import:C1210")
      (fields (field (name "MANUFACTURER") "Murata Electronics") (field (name "MPN") "GRM32ER60J227ME05L"))
      (libsource (lib "eagle-import") (part "C-USC1210"))
    )
    (comp (ref "D3")
      (value "14V")
      (footprint "eagle-import:0402_DIODE")
      (fields (field (name "MANUFACTURER") "Littlefuse") (field (name "MPN") "PESD0402-140"))
      (libsource (lib "eagle-import") (part "DIODE_ZENER0402"))
    )
    (comp (ref "D4")
      (value "14V")
      (footprint "eagle-import:0402_DIODE")
      (fields (field (name "MANUFACTURER") "Littlefuse") (field (name "MPN") "PESD0402-140"))
      (libsource (lib "eagle-import") (part "DIODE_ZENER0402"))
    )
    (comp (ref "D6")
      (value "14V")
      (footprint "eagle-import:0402_DIODE")
      (fields (field (name "MANUFACTURER") "Littlefuse") (field (name "MPN") "PESD0402-140"))
      (libsource (lib "eagle-import") (part "DIODE_ZENER0402"))
    )
    (comp (ref "D7")
      (value "14V")
      (footprint "eagle-import:0402_DIODE")
      (fields (field (name "MANUFACTURER") "Littlefuse") (field (name "MPN") "PESD0402-140"))
      (libsource (lib "eagle-import") (part "DIODE_ZENER0402"))
    )
    (comp (ref "J8")
      (value "U.FL-R-SMT")
      (footprint "eagle-import:U.FL_SMT")
      (fields (field (name "MANUFACTURER") "Hirose") (field (name "MPN") "U.FL-R-SMT-1(01)"))
      (libsource (lib "eagle-import") (part "U.FL-R-SMT"))
    )
    (comp (ref "LED1")
      (value "BLUE")
      (footprint "eagle-import:LED-0603")
      (fields (field (name "MANUFACTURER") "Rohm") (field (name "MPN") "SML-D12M8WT86"))
      (libsource (lib "eagle-import") (part "leds_LED0603"))
    )
    (comp (ref "Q1")
      (value "MOSFET-NCHANNELSMD")
      (footprint "eagle-import:SOT23-3")
      (description "MOSFET N-CH 60V 0.115A SOT-23")
      (fields (field (name "MANUFACTURER") "ON Semiconductor") (field (name "MPN") "2N7002LT1G"))
      (libsource (lib "eagle-import") (part "MOSFET-NCHANNELSMD"))
    )
    (comp (ref "Q2")
      (value "MOSFET-NCHANNELSMD")
      (footprint "eagle-import:SOT23-3")
      (description "MOSFET N-CH 60V 0.115A SOT-23")
      (fields (field (name "MANUFACTURER") "ON Semiconductor") (field (name "MPN") "2N7002LT1G"))
      (libsource (lib "eagle-import") (part "MOSFET-NCHANNELSMD"))
    )
    (comp (ref "Q3")
      (value "MOSFET-NCHANNELSMD")
      (footprint "eagle-import:SOT23-3")
      (description "MOSFET N-CH 60V 0.115A SOT-23")
      (fields (field (name "MANUFACTURER") "ON Semiconductor") (field (name "MPN") "2N7002LT1G"))
      (libsource (lib "eagle-import") (part "MOSFET-NCHANNELSMD"))
    )
    (comp (ref "Q4")
      (value "SI223DDS")
      (footprint "eagle-import:SOT23-3")
      (fields (field (name "MANUFACTURER") "Vishay Siliconix") (field (name "MPN") "SI2333DDS-T1-GE3"))
      (libsource (lib "eagle-import") (part "SI223DDS"))
    )
    (comp (ref "R6")
      (value "100")
      (footprint "eagle-import:R0603")
      (fields (field (name "MANUFACTURER") "Yageo") (field (name "MPN") "RC0603FR-07100RL"))
      (libsource (lib "eagle-import") (part "R-US_R0603"))
    )
    (comp (ref "R12")
      (value "1k")
      (footprint "eagle-import:R0603")
      (fields (field (name "MANUFACTURER") "Yageo") (field (name "MPN") "RC0603JR-071KL"))
      (libsource (lib "eagle-import") (part "R-US_R0603"))
    )
    (comp (ref "R25")
      (value "10k")
      (footprint "eagle-import:R0603")
      (fields (field (name "MANUFACTURER") "Yageo") (field (name "MPN") "RC0603JR-0710KL"))
      (libsource (lib "eagle-import") (part "R-US_R0603"))
    )
    (comp (ref "R29")
      (value "100k")
      (footprint "eagle-import:R0603")
      (fields (field (name "MANUFACTURER") "Yageo") (field (name "MPN") "RC0603JR-07100KL"))
      (libsource (lib "eagle-import") (part "R-US_R0603"))
    )
    (comp (ref "R30")
      (value "100k")
      (footprint "eagle-import:R0603")
      (fields (field (name "MANUFACTURER") "Yageo") (field (name "MPN") "RC0603JR-07100KL"))
      (libsource (lib "eagle-import") (part "R-US_R0603"))
    )
    (comp (ref "R31")
      (value "100k")
      (footprint "eagle-import:R0603")
      (fields (field (name "MANUFACTURER") "Yageo") (field (name "MPN") "RC0603JR-07100KL"))
      (libsource (lib "eagle-import") (part "R-US_R0603"))
    )
    (comp (ref "U12")
      (value "UBLOX_SARA_G350")
      (footprint "eagle-import:UBLOX_SARA_G3")
      (libsource (lib "eagle-import") (part "UBLOX_SARA_G350"))
    )
    (comp (ref "U13")
      (value "TXB0104RUT")
      (footprint "eagle-import:UQFN-12")
      (fields (field (name "MANUFACTURER") "TI") (field (name "MPN") "TXB0104RUTR"))
      (libsource (lib "eagle-import") (part "TXB0104RUT"))
    )
    (comp (ref "C19")
      (value "10nF")
      (footprint "eagle-import:RESC0603_L")
      (fields
        (field (name "DIGIKEY") "490-7194-1-ND")
        (field (name "MANUFACTURER") "Murata Electronics")
        (field (name "MPN") "GRM033R61E103KA12D")
      )
      (libsource (lib "eagle-import") (part "CAPACITOR_0603_L"))
    )
    (comp (ref "C23")
      (value "0.1uF")
      (footprint "eagle-import:RESC0603_L")
      (fields
        (field (name "DIGIKEY") "490-5405-1-ND")
        (field (name "MANUFACTURER") "Murata Electronics")
        (field (name "MPN") "GRM033R61A104ME15D")
      )
      (libsource (lib "eagle-import") (part "CAPACITOR_0603_L"))
    )
    (comp (ref "C28")
      (value ".1uF")
      (footprint "eagle-import:RESC0603_L")
      (fields (field (name "MANUFACTURER") "Murata Electronics") (field (name "MPN") "GRM033R61A104ME15D"))
      (libsource (lib "eagle-import") (part "CAPACITOR_0603_L"))
    )
    (comp (ref "C36")
      (value "4.7uF")
      (footprint "eagle-import:RESC0603_L")
      (fields
        (field (name "DIGIKEY") "490-10992-1-ND")
        (field (name "MANUFACTURER") "Murata Electronics")
        (field (name "MPN") "ZRB18AR6YA475KE05L")
      )
      (libsource (lib "eagle-import") (part "CAPACITOR_0603_L"))
    )
    (comp (ref "C37")
      (value "4.7uF")
      (footprint "eagle-import:RESC0603_L")
      (fields
        (field (name "DIGIKEY") "490-10992-1-ND")
        (field (name "MANUFACTURER") "Murata Electronics")
        (field (name "MPN") "ZRB18AR6YA475KE05L")
      )
      (libsource (lib "eagle-import") (part "CAPACITOR_0603_L"))
    )
    (comp (ref "C38")
      (value "4.7uF")
      (footprint "eagle-import:RESC0603_L")
      (fields
        (field (name "DIGIKEY") "490-10992-1-ND")
        (field (name "MANUFACTURER") "Murata Electronics")
        (field (name "MPN") "ZRB18AR6YA475KE05L")
      )
      (libsource (lib "eagle-import") (part "CAPACITOR_0603_L"))
    )
    (comp (ref "C39")
      (value "4.7uF")
      (footprint "eagle-import:RESC0603_L")
      (fields
        (field (name "DIGIKEY") "490-10992-1-ND")
        (field (name "MANUFACTURER") "Murata Electronics")
        (field (name "MPN") "ZRB18AR6YA475KE05L")
      )
      (libsource (lib "eagle-import") (part "CAPACITOR_0603_L"))
    )
    (comp (ref "C43")
      (value "10uF")
      (footprint "eagle-import:RESC0603_L")
      (fields
        (field (name "DIGIKEY") "490-12538-1-ND")
        (field (name "MANUFACTURER") "Murata Electronics")
        (field (name "MPN") "GRM188R60J106KE47D")
      )
      (libsource (lib "eagle-import") (part "CAPACITOR_0603_L"))
    )
    (comp (ref "C44")
      (value "10uF")
      (footprint "eagle-import:RESC0603_L")
      (fields
        (field (name "DIGIKEY") "490-12538-1-ND")
        (field (name "MANUFACTURER") "Murata Electronics")
        (field (name "MPN") "GRM188R60J106KE47D")
      )
      (libsource (lib "eagle-import") (part "CAPACITOR_0603_L"))
    )
    (comp (ref "C45")
      (value "10uF")
      (footprint "eagle-import:RESC0603_L")
      (fields
        (field (name "DIGIKEY") "490-12538-1-ND")
        (field (name "MANUFACTURER") "Murata Electronics")
        (field (name "MPN") "GRM188R60J106KE47D")
      )
      (libsource (lib "eagle-import") (part "CAPACITOR_0603_L"))
    )
    (comp (ref "D1")
      (value "GREEN")
      (footprint "eagle-import:LED-0603")
      (libsource (lib "eagle-import") (part "LED0603"))
    )
    (comp (ref "IC1")
      (value "TPS6300")
      (footprint "eagle-import:DRC-S-PVSON-N10")
      (fields (field (name "MPN") "TPS63000DRCTG4"))
      (libsource (lib "eagle-import") (part "TPS6300"))
    )
    (comp (ref "L3")
      (value "2.2uH")
      (footprint "eagle-import:RESC0603_M")
      (fields
        (field (name "DIGIKEY") "490-14478-1-ND")
        (field (name "MANUFACTURER") "Murata Electronics")
        (field (name "MPN") "LQM18PN2R2MGHD")
      )
      (libsource (lib "eagle-import") (part "INDUCTOR_0603_M"))
    )
    (comp (ref "R5")
      (value "100")
      (footprint "eagle-import:R0603")
      (fields
        (field (name "DIGIKEY") "311-100HRCT-ND")
        (field (name "MANUFACTURER") "Yageo")
        (field (name "MPN") "RC0603FR-07100RL")
      )
      (libsource (lib "eagle-import") (part "R-US_R0603"))
    )
    (comp (ref "R11")
      (value "1k")
      (footprint "eagle-import:R0603")
      (fields
        (field (name "DIGIKEY") "311-1.0KGRCT-ND")
        (field (name "MANUFACTURER") "Yageo")
        (field (name "MPN") "RC0603JR-071KL")
      )
      (libsource (lib "eagle-import") (part "R-US_R0603"))
    )
    (comp (ref "R13")
      (value "2k")
      (footprint "eagle-import:R0603")
      (fields
        (field (name "DIGIKEY") "311-2.00KHRCT-ND")
        (field (name "MANUFACTURER") "Yageo")
        (field (name "MPN") "RC0603FR-072KL")
      )
      (libsource (lib "eagle-import") (part "R-US_R0603"))
    )
    (comp (ref "R32")
      (value "200k")
      (footprint "eagle-import:R0603")
      (fields
        (field (name "DIGIKEY") "311-200KGRTR-ND")
        (field (name "MANUFACTURER") "Yageo")
        (field (name "MPN") "RC0603JR-07200KL")
      )
      (libsource (lib "eagle-import") (part "R-US_R0603"))
    )
    (comp (ref "R36")
      (value "1.3M")
      (footprint "eagle-import:R0603")
      (fields
        (field (name "DIGIKEY") "YAG3326CT-ND")
        (field (name "MANUFACTURER") "Yageo")
        (field (name "MPN") "RC0603FR-071M3L")
      )
      (libsource (lib "eagle-import") (part "R-US_R0603"))
    )
    (comp (ref "R37")
      (value "2.2M")
      (footprint "eagle-import:R0603")
      (fields
        (field (name "DIGIKEY") "311-2.2MGRCT-ND")
        (field (name "MANUFACTURER") "Yageo")
        (field (name "MPN") "RC0603JR-072M2L")
      )
      (libsource (lib "eagle-import") (part "R-US_R0603"))
    )
    (comp (ref "R38")
      (value "10M")
      (footprint "eagle-import:R0603")
      (fields
        (field (name "DIGIKEY") "311-10MGRCT-ND")
        (field (name "MANUFACTURER") "Yageo")
        (field (name "MPN") "RC0603JR-0710ML")
      )
      (libsource (lib "eagle-import") (part "R-US_R0603"))
    )
    (comp (ref "U5")
      (value "MAX8887EZK33+T")
      (footprint "eagle-import:SOT-23-5")
      (libsource (lib "eagle-import") (part "MAX8887EZK33+T"))
    )
    (comp (ref "U6")
      (value "MCP73831")
      (footprint "eagle-import:DFN-8-MCP")
      (fields (field (name "MANUFACTURER") "Microchip Technology") (field (name "MPN") "MCP73831T-2ACI/MC"))
      (libsource (lib "eagle-import") (part "MCP73831"))
    )
  )
  (nets
    (net (code "1") (name "5V") (class "Default")
      (node (ref "C36") (pin "1") (pinfunction "1_1") (pintype "passive"))
      (node (ref "FB1") (pin "P$2") (pinfunction "P$2_P$2") (pintype "bidirectional"))
      (node (ref "J2") (pin "1") (pinfunction "+5V_1") (pintype "bidirectional"))
      (node (ref "R11") (pin "2") (pinfunction "2_2") (pintype "passive"))
      (node (ref "R35") (pin "1") (pinfunction "1_1") (pintype "passive"))
      (node (ref "U15") (pin "6") (pinfunction "V+_6") (pintype "power_in"))
      (node (ref "U20") (pin "6") (pinfunction "V+_6") (pintype "power_in"))
      (node (ref "U21") (pin "6") (pinfunction "V+_6") (pintype "power_in"))
      (node (ref "U22") (pin "6") (pinfunction "V+_6") (pintype "power_in"))
      (node (ref "U6") (pin "1") (pinfunction "VDD/1_1") (pintype "power_in"))
      (node (ref "U6") (pin "2") (pinfunction "VDD/2_2") (pintype "power_in"))
    )
    (net (code "2") (name "ANT") (class "Default")
      (node (ref "A1") (pin "0") (pinfunction "1_0") (pintype "output"))
      (node (ref "L1") (pin "2") (pinfunction "2_2") (pintype "passive"))
    )
    (net (code "3") (name "BAT") (class "Default")
      (node (ref "C37") (pin "1") (pinfunction "1_1") (pintype "passive"))
      (node (ref "C43") (pin "1") (pinfunction "1_1") (pintype "passive"))
      (node (ref "IC1") (pin "5") (pinfunction "VIN_5") (pintype "input"))
      (node (ref "JP1") (pin "VCC") (pinfunction "2_VCC") (pintype "passive"))
      (node (ref "R16") (pin "1") (pinfunction "1_1") (pintype "passive"))
      (node (ref "R34") (pin "1") (pinfunction "1_1") (pintype "passive"))
      (node (ref "R38") (pin "2") (pinfunction "2_2") (pintype "passive"))
      (node (ref "R5") (pin "2") (pinfunction "2_2") (pintype "passive"))
      (node (ref "U6") (pin "3") (pinfunction "VBAT/3_3") (pintype "power_in"))
      (node (ref "U6") (pin "4") (pinfunction "VBAT/4_4") (pintype "power_in"))
      (node (ref "U8") (pin "5") (pinfunction "WDS_5") (pintype "bidirectional"))
      (node (ref "U8") (pin "8") (pinfunction "VCC_8") (pintype "bidirectional"))
    )
    (net (code "4") (name "BATIN") (class "Default")
      (node (ref "C23") (pin "2") (pinfunction "2_2") (pintype "passive"))
      (node (ref "R37") (pin "2") (pinfunction "2_2") (pintype "passive"))
      (node (ref "R38") (pin "1") (pinfunction "1_1") (pintype "passive"))
      (node (ref "TP22") (pin "P$1") (pinfunction "TESTPOINT_P$1") (pintype "bidirectional"))
      (node (ref "U9") (pin "R24") (pinfunction "P1.06_R24") (pintype "bidirectional"))
    )
    (net (code "5") (name "CLK1") (class "Default")
      (node (ref "J3") (pin "C3") (pinfunction "C3(CLK)_C3") (pintype "bidirectional"))
      (node (ref "U22") (pin "2") (pinfunction "NO1_2") (pintype "passive"))
    )
    (net (code "6") (name "CLK2") (class "Default")
      (node (ref "J4") (pin "C3") (pinfunction "C3(CLK)_C3") (pintype "bidirectional"))
      (node (ref "U22") (pin "9") (pinfunction "NO2_9") (pintype "passive"))
    )
    (net (code "7") (name "CLK3") (class "Default")
      (node (ref "J5") (pin "C3") (pinfunction "C3(CLK)_C3") (pintype "bidirectional"))
      (node (ref "U22") (pin "4") (pinfunction "NO3_4") (pintype "passive"))
    )
    (net (code "8") (name "CLK4") (class "Default")
      (node (ref "J6") (pin "C3") (pinfunction "C3(CLK)_C3") (pintype "bidirectional"))
      (node (ref "U22") (pin "7") (pinfunction "NO4_7") (pintype "passive"))
    )
    (net (code "9") (name "CLK_SIM") (class "Default")
      (node (ref "C12") (pin "1") (pinfunction "1_1") (pintype "passive"))
      (node (ref "D7") (pin "CATHODE") (pinfunction "CATHODE_CATHODE") (pintype "bidirectional"))
      (node (ref "U12") (pin "38") (pinfunction "SIM_CLK_38") (pintype "bidirectional"))
      (node (ref "U22") (pin "8") (pinfunction "COM_8") (pintype "passive"))
    )
    (net (code "10") (name "GND") (class "Default")
      (node (ref "A1") (pin "1") (pinfunction "2_1") (pintype "power_in"))
      (node (ref "A1") (pin "2") (pinfunction "2_2") (pintype "power_in"))
      (node (ref "A1") (pin "3") (pinfunction "2_3") (pintype "power_in"))
      (node (ref "A1") (pin "4") (pinfunction "2_4") (pintype "power_in"))
      (node (ref "B1") (pin "-") (pinfunction "-_-") (pintype "bidirectional"))
      (node (ref "C1") (pin "1") (pinfunction "1_1") (pintype "passive"))
      (node (ref "C13") (pin "2") (pinfunction "2_2") (pintype "passive"))
      (node (ref "C14") (pin "2") (pinfunction "2_2") (pintype "passive"))
      (node (ref "C15") (pin "2") (pinfunction "2_2") (pintype "passive"))
      (node (ref "C16") (pin "1") (pinfunction "1_1") (pintype "passive"))
      (node (ref "C17") (pin "1") (pinfunction "1_1") (pintype "passive"))
      (node (ref "C18") (pin "2") (pinfunction "2_2") (pintype "passive"))
      (node (ref "C19") (pin "2") (pinfunction "2_2") (pintype "passive"))
      (node (ref "C2") (pin "1") (pinfunction "1_1") (pintype "passive"))
      (node (ref "C20") (pin "2") (pinfunction "2_2") (pintype "passive"))
      (node (ref "C21") (pin "2") (pinfunction "2_2") (pintype "passive"))
      (node (ref "C22") (pin "1") (pinfunction "1_1") (pintype "passive"))
      (node (ref "C23") (pin "1") (pinfunction "1_1") (pintype "passive"))
      (node (ref "C24") (pin "2") (pinfunction "2_2") (pintype "passive"))
      (node (ref "C25") (pin "2") (pinfunction "2_2") (pintype "passive"))
      (node (ref "C26") (pin "2") (pinfunction "2_2") (pintype "passive"))
      (node (ref "C27") (pin "2") (pinfunction "2_2") (pintype "passive"))
      (node (ref "C28") (pin "2") (pinfunction "2_2") (pintype "passive"))
      (node (ref "C29") (pin "2") (pinfunction "2_2") (pintype "passive"))
      (node (ref "C3") (pin "1") (pinfunction "1_1") (pintype "passive"))
      (node (ref "C30") (pin "2") (pinfunction "2_2") (pintype "passive"))
      (node (ref "C31") (pin "2") (pinfunction "2_2") (pintype "passive"))
      (node (ref "C32") (pin "2") (pinfunction "2_2") (pintype "passive"))
      (node (ref "C33") (pin "2") (pinfunction "2_2") (pintype "passive"))
      (node (ref "C34") (pin "2") (pinfunction "2_2") (pintype "passive"))
      (node (ref "C35") (pin "2") (pinfunction "2_2") (pintype "passive"))
      (node (ref "C36") (pin "2") (pinfunction "2_2") (pintype "passive"))
      (node (ref "C37") (pin "2") (pinfunction "2_2") (pintype "passive"))
      (node (ref "C38") (pin "2") (pinfunction "2_2") (pintype "passive"))
      (node (ref "C39") (pin "2") (pinfunction "2_2") (pintype "passive"))
      (node (ref "C4") (pin "1") (pinfunction "1_1") (pintype "passive"))
      (node (ref "C40") (pin "2") (pinfunction "2_2") (pintype "passive"))
      (node (ref "C41") (pin "2") (pinfunction "2_2") (pintype "passive"))
      (node (ref "C42") (pin "1") (pinfunction "1_1") (pintype "passive"))
      (node (ref "C43") (pin "2") (pinfunction "2_2") (pintype "passive"))
      (node (ref "C44") (pin "2") (pinfunction "2_2") (pintype "passive"))
      (node (ref "C45") (pin "2") (pinfunction "2_2") (pintype "passive"))
      (node (ref "C46") (pin "2") (pinfunction "2_2") (pintype "passive"))
      (node (ref "C47") (pin "2") (pinfunction "2_2") (pintype "passive"))
      (node (ref "C6") (pin "2") (pinfunction "2_2") (pintype "passive"))
      (node (ref "C7") (pin "2") (pinfunction "2_2") (pintype "passive"))
      (node (ref "C8") (pin "2") (pinfunction "2_2") (pintype "passive"))
      (node (ref "IC1") (pin "3") (pinfunction "PGND_3") (pintype "power_in"))
      (node (ref "IC1") (pin "9") (pinfunction "GND_9") (pintype "power_in"))
      (node (ref "J1") (pin "6") (pinfunction "GND_6") (pintype "bidirectional"))
      (node (ref "J1") (pin "B") (pinfunction "B_B") (pintype "bidirectional"))
      (node (ref "J1") (pin "MOUNT0") (pinfunction "GND_MOUNT0") (pintype "bidirectional"))
      (node (ref "J1") (pin "MOUNT1") (pinfunction "GND_MOUNT1") (pintype "bidirectional"))
      (node (ref "J1") (pin "MOUNT2") (pinfunction "GND_MOUNT2") (pintype "bidirectional"))
      (node (ref "J1") (pin "MOUNT3") (pinfunction "GND_MOUNT3") (pintype "bidirectional"))
      (node (ref "J2") (pin "5") (pinfunction "GND_5") (pintype "bidirectional"))
      (node (ref "J3") (pin "C5") (pinfunction "C5(GND)_C5") (pintype "bidirectional"))
      (node (ref "J4") (pin "C5") (pinfunction "C5(GND)_C5") (pintype "bidirectional"))
      (node (ref "J5") (pin "C5") (pinfunction "C5(GND)_C5") (pintype "bidirectional"))
      (node (ref "J6") (pin "C5") (pinfunction "C5(GND)_C5") (pintype "bidirectional"))
      (node (ref "J7") (pin "5") (pinfunction "GND_5") (pintype "bidirectional"))
      (node (ref "J8") (pin "GND1") (pinfunction "P$2_GND1") (pintype "bidirectional"))
      (node (ref "J8") (pin "GND2") (pinfunction "P$2_GND2") (pintype "bidirectional"))
      (node (ref "JP1") (pin "GND") (pinfunction "1_GND") (pintype "passive"))
      (node (ref "Q1") (pin "2") (pinfunction "S_2") (pintype "passive"))
      (node (ref "Q2") (pin "2") (pinfunction "S_2") (pintype "passive"))
      (node (ref "Q3") (pin "2") (pinfunction "S_2") (pintype "passive"))
      (node (ref "R13") (pin "1") (pinfunction "1_1") (pintype "passive"))
      (node (ref "R26") (pin "1") (pinfunction "1_1") (pintype "passive"))
      (node (ref "R27") (pin "2") (pinfunction "2_2") (pintype "passive"))
      (node (ref "R30") (pin "1") (pinfunction "1_1") (pintype "passive"))
      (node (ref "R31") (pin "1") (pinfunction "1_1") (pintype "passive"))
      (node (ref "R32") (pin "1") (pinfunction "1_1") (pintype "passive"))
      (node (ref "R33") (pin "2") (pinfunction "2_2") (pintype "passive"))
      (node (ref "R37") (pin "1") (pinfunction "1_1") (pintype "passive"))
      (node (ref "TP28") (pin "P$1") (pinfunction "TESTPOINT_P$1") (pintype "bidirectional"))
      (node (ref "U1") (pin "10") (pinfunction "EXTI_10") (pintype "bidirectional"))
      (node (ref "U1") (pin "3") (pinfunction "~{EXTR}_3") (pintype "bidirectional"))
      (node (ref "U1") (pin "GND") (pinfunction "VSS_GND") (pintype "bidirectional"))
      (node (ref "U10") (pin "4") (pinfunction "GND_4") (pintype "bidirectional"))
      (node (ref "U11") (pin "4") (pinfunction "GND_4") (pintype "bidirectional"))
      (node (ref "U12") (pin "1") (pinfunction "GND_1") (pintype "bidirectional"))
      (node (ref "U12") (pin "14") (pinfunction "GND_14") (pintype "bidirectional"))
      (node (ref "U12") (pin "20") (pinfunction "GND_20") (pintype "bidirectional"))
      (node (ref "U12") (pin "21") (pinfunction "GND_21") (pintype "bidirectional"))
      (node (ref "U12") (pin "22") (pinfunction "GND_22") (pintype "bidirectional"))
      (node (ref "U12") (pin "3") (pinfunction "GND_3") (pintype "bidirectional"))
      (node (ref "U12") (pin "30") (pinfunction "GND_30") (pintype "bidirectional"))
      (node (ref "U12") (pin "32") (pinfunction "GND_32") (pintype "bidirectional"))
      (node (ref "U12") (pin "33") (pinfunction "GND_33") (pintype "bidirectional"))
      (node (ref "U12") (pin "43") (pinfunction "GND_43") (pintype "bidirectional"))
      (node (ref "U12") (pin "5") (pinfunction "GND_5") (pintype "bidirectional"))
      (node (ref "U12") (pin "50") (pinfunction "GND_50") (pintype "bidirectional"))
      (node (ref "U12") (pin "54") (pinfunction "GND_54") (pintype "bidirectional"))
      (node (ref "U12") (pin "55") (pinfunction "GND_55") (pintype "bidirectional"))
      (node (ref "U12") (pin "57") (pinfunction "GND_57") (pintype "bidirectional"))
      (node (ref "U12") (pin "58") (pinfunction "GND_58") (pintype "bidirectional"))
      (node (ref "U12") (pin "59") (pinfunction "GND_59") (pintype "bidirectional"))
      (node (ref "U12") (pin "60") (pinfunction "GND_60") (pintype "bidirectional"))
      (node (ref "U12") (pin "61") (pinfunction "GND_61") (pintype "bidirectional"))
      (node (ref "U12") (pin "63") (pinfunction "GND_63") (pintype "bidirectional"))
      (node (ref "U12") (pin "64") (pinfunction "GND_64") (pintype "bidirectional"))
      (node (ref "U12") (pin "65") (pinfunction "GND_65") (pintype "bidirectional"))
      (node (ref "U12") (pin "66") (pinfunction "GND_66") (pintype "bidirectional"))
      (node (ref "U12") (pin "67") (pinfunction "GND_67") (pintype "bidirectional"))
      (node (ref "U12") (pin "68") (pinfunction "GND_68") (pintype "bidirectional"))
      (node (ref "U12") (pin "69") (pinfunction "GND_69") (pintype "bidirectional"))
      (node (ref "U12") (pin "70") (pinfunction "GND_70") (pintype "bidirectional"))
      (node (ref "U12") (pin "71") (pinfunction "GND_71") (pintype "bidirectional"))
      (node (ref "U12") (pin "72") (pinfunction "GND_72") (pintype "bidirectional"))
      (node (ref "U12") (pin "73") (pinfunction "GND_73") (pintype "bidirectional"))
      (node (ref "U12") (pin "74") (pinfunction "GND_74") (pintype "bidirectional"))
      (node (ref "U12") (pin "75") (pinfunction "GND_75") (pintype "bidirectional"))
      (node (ref "U12") (pin "76") (pinfunction "GND_76") (pintype "bidirectional"))
      (node (ref "U12") (pin "77") (pinfunction "GND_77") (pintype "bidirectional"))
      (node (ref "U12") (pin "78") (pinfunction "GND_78") (pintype "bidirectional"))
      (node (ref "U12") (pin "79") (pinfunction "GND_79") (pintype "bidirectional"))
      (node (ref "U12") (pin "80") (pinfunction "GND_80") (pintype "bidirectional"))
      (node (ref "U12") (pin "81") (pinfunction "GND_81") (pintype "bidirectional"))
      (node (ref "U12") (pin "82") (pinfunction "GND_82") (pintype "bidirectional"))
      (node (ref "U12") (pin "83") (pinfunction "GND_83") (pintype "bidirectional"))
      (node (ref "U12") (pin "84") (pinfunction "GND_84") (pintype "bidirectional"))
      (node (ref "U12") (pin "85") (pinfunction "GND_85") (pintype "bidirectional"))
      (node (ref "U12") (pin "86") (pinfunction "GND_86") (pintype "bidirectional"))
      (node (ref "U12") (pin "87") (pinfunction "GND_87") (pintype "bidirectional"))
      (node (ref "U12") (pin "88") (pinfunction "GND_88") (pintype "bidirectional"))
      (node (ref "U12") (pin "89") (pinfunction "GND_89") (pintype "bidirectional"))
      (node (ref "U12") (pin "9") (pinfunction "DTR_9") (pintype "bidirectional"))
      (node (ref "U12") (pin "90") (pinfunction "GND_90") (pintype "bidirectional"))
      (node (ref "U12") (pin "91") (pinfunction "GND_91") (pintype "bidirectional"))
      (node (ref "U12") (pin "92") (pinfunction "GND_92") (pintype "bidirectional"))
      (node (ref "U12") (pin "93") (pinfunction "GND_93") (pintype "bidirectional"))
      (node (ref "U12") (pin "94") (pinfunction "GND_94") (pintype "bidirectional"))
      (node (ref "U12") (pin "95") (pinfunction "GND_95") (pintype "bidirectional"))
      (node (ref "U12") (pin "96") (pinfunction "GND_96") (pintype "bidirectional"))
      (node (ref "U13") (pin "6") (pinfunction "GND_6") (pintype "bidirectional"))
      (node (ref "U15") (pin "3") (pinfunction "GND_3") (pintype "power_in"))
      (node (ref "U2") (pin "1") (pinfunction "GND_1") (pintype "power_in"))
      (node (ref "U2") (pin "4") (pinfunction "GND_4") (pintype "power_in"))
      (node (ref "U20") (pin "3") (pinfunction "GND_3") (pintype "power_in"))
      (node (ref "U21") (pin "3") (pinfunction "GND_3") (pintype "power_in"))
      (node (ref "U22") (pin "3") (pinfunction "GND_3") (pintype "power_in"))
      (node (ref "U3") (pin "13") (pinfunction "GND_13") (pintype "bidirectional"))
      (node (ref "U3") (pin "5") (pinfunction "GND_5") (pintype "bidirectional"))
      (node (ref "U4") (pin "2") (pinfunction "GND_2") (pintype "power_in"))
      (node (ref "U4") (pin "3") (pinfunction "GND_3") (pintype "power_in"))
      (node (ref "U4") (pin "5") (pinfunction "GND_5") (pintype "power_in"))
      (node (ref "U5") (pin "2") (pinfunction "GND_2") (pintype "bidirectional"))
      (node (ref "U6") (pin "6") (pinfunction "VSS_6") (pintype "power_in"))
      (node (ref "U6") (pin "GND") (pinfunction "GND_GND") (pintype "power_in"))
      (node (ref "U7") (pin "1") (pinfunction "GND_1") (pintype "bidirectional"))
      (node (ref "U7") (pin "10") (pinfunction "GND_10") (pintype "bidirectional"))
      (node (ref "U7") (pin "12") (pinfunction "GND_12") (pintype "bidirectional"))
      (node (ref "U8") (pin "4") (pinfunction "GND_4") (pintype "bidirectional"))
      (node (ref "U9") (pin "AD2") (pinfunction "VBUS_AD2") (pintype "bidirectional"))
      (node (ref "U9") (pin "B7") (pinfunction "VSS_B7") (pintype "bidirectional"))
      (node (ref "U9") (pin "F23") (pinfunction "VSS_PA_F23") (pintype "bidirectional"))
      (node (ref "U9") (pin "GND") (pinfunction "VSS_GND") (pintype "bidirectional"))
      (node (ref "X4") (pin "2") (pinfunction "GND_2") (pintype "bidirectional"))
      (node (ref "X4") (pin "4") (pinfunction "GND_4") (pintype "bidirectional"))
    )
    (net (code "11") (name "GPS_PWR_EN") (class "Default")
      (node (ref "R26") (pin "2") (pinfunction "2_2") (pintype "passive"))
      (node (ref "TP10") (pin "P$1") (pinfunction "TESTPOINT_P$1") (pintype "bidirectional"))
      (node (ref "U11") (pin "3") (pinfunction "EN_3") (pintype "bidirectional"))
      (node (ref "U9") (pin "AC15") (pinfunction "P0.19_AC15") (pintype "bidirectional"))
    )
    (net (code "12") (name "GPS_RXD") (class "Default")
      (node (ref "L6") (pin "2") (pinfunction "2_2") (pintype "passive"))
      (node (ref "TP1") (pin "P$1") (pinfunction "TESTPOINT_P$1") (pintype "bidirectional"))
      (node (ref "U9") (pin "M2") (pinfunction "P0.07_M2") (pintype "bidirectional"))
    )
    (net (code "13") (name "GPS_TXD") (class "Default")
      (node (ref "L5") (pin "2") (pinfunction "2_2") (pintype "passive"))
      (node (ref "TP2") (pin "P$1") (pinfunction "TESTPOINT_P$1") (pintype "bidirectional"))
      (node (ref "U9") (pin "N1") (pinfunction "P0.08_N1") (pintype "bidirectional"))
    )
    (net (code "14") (name "GPS_VCC") (class "Default")
      (node (ref "C17") (pin "2") (pinfunction "2_2") (pintype "passive"))
      (node (ref "C22") (pin "2") (pinfunction "2_2") (pintype "passive"))
      (node (ref "C42") (pin "2") (pinfunction "2_2") (pintype "passive"))
      (node (ref "R10") (pin "2") (pinfunction "2_2") (pintype "passive"))
      (node (ref "U11") (pin "1") (pinfunction "VLOAD_1") (pintype "bidirectional"))
      (node (ref "U11") (pin "2") (pinfunction "VLOAD_2") (pintype "bidirectional"))
      (node (ref "U7") (pin "6") (pinfunction "V_BCKP_6") (pintype "bidirectional"))
      (node (ref "U7") (pin "7") (pinfunction "VCC_IO_7") (pintype "bidirectional"))
      (node (ref "U7") (pin "8") (pinfunction "VCC_8") (pintype "bidirectional"))
    )
    (net (code "15") (name "GSM_CTS") (class "Default")
      (node (ref "TP16") (pin "P$1") (pinfunction "TESTPOINT_P$1") (pintype "bidirectional"))
      (node (ref "U13") (pin "10") (pinfunction "B1_10") (pintype "bidirectional"))
      (node (ref "U9") (pin "A12") (pinfunction "P0.02/AIN0_A12") (pintype "bidirectional"))
    )
    (net (code "16") (name "GSM_GATED") (class "Default")
      (node (ref "C13") (pin "1") (pinfunction "1_1") (pintype "passive"))
      (node (ref "C20") (pin "1") (pinfunction "1_1") (pintype "passive"))
      (node (ref "C30") (pin "1") (pinfunction "1_1") (pintype "passive"))
      (node (ref "C47") (pin "1") (pinfunction "1_1") (pintype "passive"))
      (node (ref "Q4") (pin "3") (pinfunction "D_3") (pintype "passive"))
      (node (ref "R12") (pin "2") (pinfunction "2_2") (pintype "passive"))
      (node (ref "U12") (pin "51") (pinfunction "VCC_51") (pintype "bidirectional"))
      (node (ref "U12") (pin "52") (pinfunction "VCC_52") (pintype "bidirectional"))
      (node (ref "U12") (pin "53") (pinfunction "VCC_53") (pintype "bidirectional"))
    )
    (net (code "17") (name "GSM_LED") (class "Default")
      (node (ref "Q3") (pin "1") (pinfunction "G_1") (pintype "passive"))
      (node (ref "R31") (pin "2") (pinfunction "2_2") (pintype "passive"))
      (node (ref "U12") (pin "16") (pinfunction "GPIO1_16") (pintype "bidirectional"))
    )
    (net (code "18") (name "GSM_POWER") (class "Default")
      (node (ref "Q1") (pin "1") (pinfunction "G_1") (pintype "passive"))
      (node (ref "TP17") (pin "P$1") (pinfunction "TESTPOINT_P$1") (pintype "bidirectional"))
      (node (ref "U9") (pin "B13") (pinfunction "P0.03/AIN1_B13") (pintype "bidirectional"))
    )
    (net (code "19") (name "GSM_POWER_GATE") (class "Default")
      (node (ref "R30") (pin "2") (pinfunction "2_2") (pintype "passive"))
      (node (ref "R6") (pin "2") (pinfunction "2_2") (pintype "passive"))
    )
    (net (code "20") (name "GSM_RST") (class "Default")
      (node (ref "Q2") (pin "1") (pinfunction "G_1") (pintype "passive"))
      (node (ref "TP19") (pin "P$1") (pinfunction "TESTPOINT_P$1") (pintype "bidirectional"))
      (node (ref "U9") (pin "A10") (pinfunction "P0.29/AIN5_A10") (pintype "bidirectional"))
    )
    (net (code "21") (name "GSM_RTS") (class "Default")
      (node (ref "TP18") (pin "P$1") (pinfunction "TESTPOINT_P$1") (pintype "bidirectional"))
      (node (ref "U13") (pin "9") (pinfunction "B2_9") (pintype "bidirectional"))
      (node (ref "U9") (pin "B11") (pinfunction "P0.28/AIN4_B11") (pintype "bidirectional"))
    )
    (net (code "22") (name "GSM_RX") (class "Default")
      (node (ref "U13") (pin "8") (pinfunction "B3_8") (pintype "bidirectional"))
      (node (ref "U9") (pin "B9") (pinfunction "P0.30/AIN6_B9") (pintype "bidirectional"))
    )
    (net (code "23") (name "GSM_TX") (class "Default")
      (node (ref "TP20") (pin "P$1") (pinfunction "TESTPOINT_P$1") (pintype "bidirectional"))
      (node (ref "U13") (pin "7") (pinfunction "B4_7") (pintype "bidirectional"))
      (node (ref "U9") (pin "A8") (pinfunction "P0.31/AIN7_A8") (pintype "bidirectional"))
    )
    (net (code "24") (name "IO1") (class "Default")
      (node (ref "J3") (pin "C7") (pinfunction "C7(IO)_C7") (pintype "bidirectional"))
      (node (ref "U21") (pin "2") (pinfunction "NO1_2") (pintype "passive"))
    )
    (net (code "25") (name "IO2") (class "Default")
      (node (ref "J4") (pin "C7") (pinfunction "C7(IO)_C7") (pintype "bidirectional"))
      (node (ref "U21") (pin "9") (pinfunction "NO2_9") (pintype "passive"))
    )
    (net (code "26") (name "IO3") (class "Default")
      (node (ref "J5") (pin "C7") (pinfunction "C7(IO)_C7") (pintype "bidirectional"))
      (node (ref "U21") (pin "4") (pinfunction "NO3_4") (pintype "passive"))
    )
    (net (code "27") (name "IO4") (class "Default")
      (node (ref "J6") (pin "C7") (pinfunction "C7(IO)_C7") (pintype "bidirectional"))
      (node (ref "U21") (pin "7") (pinfunction "NO4_7") (pintype "passive"))
    )
    (net (code "28") (name "IO_SIM") (class "Default")
      (node (ref "C9") (pin "1") (pinfunction "1_1") (pintype "passive"))
      (node (ref "D4") (pin "CATHODE") (pinfunction "CATHODE_CATHODE") (pintype "bidirectional"))
      (node (ref "U12") (pin "39") (pinfunction "SIM_IO_39") (pintype "bidirectional"))
      (node (ref "U21") (pin "8") (pinfunction "COM_8") (pintype "passive"))
    )
    (net (code "29") (name "LED_NRF_BLUE") (class "Default")
      (node (ref "R9") (pin "2") (pinfunction "2_2") (pintype "passive"))
      (node (ref "U9") (pin "J1") (pinfunction "P0.04/AIN2_J1") (pintype "bidirectional"))
    )
    (net (code "30") (name "LED_NRF_GREEN") (class "Default")
      (node (ref "R8") (pin "2") (pinfunction "2_2") (pintype "passive"))
      (node (ref "U9") (pin "L1") (pinfunction "P0.06_L1") (pintype "bidirectional"))
    )
    (net (code "31") (name "LED_NRF_RED") (class "Default")
      (node (ref "R7") (pin "2") (pinfunction "2_2") (pintype "passive"))
      (node (ref "U9") (pin "K2") (pinfunction "P0.05/AIN3_K2") (pintype "bidirectional"))
    )
    (net (code "32") (name "MUX_EN") (class "Default")
      (node (ref "R21") (pin "2") (pinfunction "2_2") (pintype "passive"))
      (node (ref "R22") (pin "2") (pinfunction "2_2") (pintype "passive"))
      (node (ref "R23") (pin "2") (pinfunction "2_2") (pintype "passive"))
      (node (ref "R24") (pin "2") (pinfunction "2_2") (pintype "passive"))
      (node (ref "TP9") (pin "P$1") (pinfunction "TESTPOINT_P$1") (pintype "bidirectional"))
      (node (ref "U15") (pin "5") (pinfunction "EN_5") (pintype "input"))
      (node (ref "U20") (pin "5") (pinfunction "EN_5") (pintype "input"))
      (node (ref "U21") (pin "5") (pinfunction "EN_5") (pintype "input"))
      (node (ref "U22") (pin "5") (pinfunction "EN_5") (pintype "input"))
      (node (ref "U9") (pin "AD12") (pinfunction "P0.17_AD12") (pintype "bidirectional"))
    )
    (net (code "33") (name "MUX_SEL1") (class "Default")
      (node (ref "TP23") (pin "P$1") (pinfunction "TESTPOINT_P$1") (pintype "bidirectional"))
      (node (ref "U15") (pin "1") (pinfunction "A0_1") (pintype "input"))
      (node (ref "U20") (pin "1") (pinfunction "A0_1") (pintype "input"))
      (node (ref "U21") (pin "1") (pinfunction "A0_1") (pintype "input"))
      (node (ref "U22") (pin "1") (pinfunction "A0_1") (pintype "input"))
      (node (ref "U9") (pin "R1") (pinfunction "P1.09_R1") (pintype "bidirectional"))
    )
    (net (code "34") (name "MUX_SEL2") (class "Default")
      (node (ref "TP26") (pin "P$1") (pinfunction "TESTPOINT_P$1") (pintype "bidirectional"))
      (node (ref "U15") (pin "10") (pinfunction "A1_10") (pintype "input"))
      (node (ref "U20") (pin "10") (pinfunction "A1_10") (pintype "input"))
      (node (ref "U21") (pin "10") (pinfunction "A1_10") (pintype "input"))
      (node (ref "U22") (pin "10") (pinfunction "A1_10") (pintype "input"))
      (node (ref "U9") (pin "AC21") (pinfunction "P0.25_AC21") (pintype "bidirectional"))
    )
    (net (code "35") (name "NRF_GPIO_0") (class "Default")
      (node (ref "TP29") (pin "P$1") (pinfunction "TESTPOINT_P$1") (pintype "bidirectional"))
      (node (ref "U9") (pin "H2") (pinfunction "P0.27_H2") (pintype "bidirectional"))
    )
    (net (code "36") (name "NRF_GPIO_1") (class "Default")
      (node (ref "TP30") (pin "P$1") (pinfunction "TESTPOINT_P$1") (pintype "bidirectional"))
      (node (ref "U9") (pin "G1") (pinfunction "P0.26_G1") (pintype "bidirectional"))
    )
    (net (code "37") (name "NRF_MISO") (class "Default")
      (node (ref "J1") (pin "7") (pinfunction "DATA0/MISO_7") (pintype "bidirectional"))
      (node (ref "R20") (pin "1") (pinfunction "1_1") (pintype "passive"))
      (node (ref "TP7") (pin "P$1") (pinfunction "TESTPOINT_P$1") (pintype "bidirectional"))
      (node (ref "U1") (pin "6") (pinfunction "SDO_6") (pintype "bidirectional"))
      (node (ref "U9") (pin "AD10") (pinfunction "P0.15_AD10") (pintype "bidirectional"))
    )
    (net (code "38") (name "NRF_MOSI") (class "Default")
      (node (ref "J1") (pin "3") (pinfunction "CMD/MOSI_3") (pintype "bidirectional"))
      (node (ref "R18") (pin "1") (pinfunction "1_1") (pintype "passive"))
      (node (ref "TP5") (pin "P$1") (pinfunction "TESTPOINT_P$1") (pintype "bidirectional"))
      (node (ref "U1") (pin "9") (pinfunction "SDI_9") (pintype "bidirectional"))
      (node (ref "U9") (pin "AD8") (pinfunction "P0.13_AD8") (pintype "bidirectional"))
    )
    (net (code "39") (name "NRF_SCK") (class "Default")
      (node (ref "J1") (pin "5") (pinfunction "CLK_5") (pintype "bidirectional"))
      (node (ref "U1") (pin "7") (pinfunction "SCL_7") (pintype "bidirectional"))
    )
    (net (code "40") (name "NRF_SWDCLK") (class "Default")
      (node (ref "J7") (pin "4") (pinfunction "SWDCLK_4") (pintype "bidirectional"))
      (node (ref "TP15") (pin "P$1") (pinfunction "TESTPOINT_P$1") (pintype "bidirectional"))
      (node (ref "U9") (pin "AA24") (pinfunction "SWDCLK_AA24") (pintype "bidirectional"))
    )
    (net (code "41") (name "NRF_SWDIO") (class "Default")
      (node (ref "J7") (pin "2") (pinfunction "SWDIO_2") (pintype "bidirectional"))
      (node (ref "TP14") (pin "P$1") (pinfunction "TESTPOINT_P$1") (pintype "bidirectional"))
      (node (ref "U9") (pin "AC24") (pinfunction "SWDIO_AC24") (pintype "bidirectional"))
    )
    (net (code "42") (name "Net-(C10-Pad2)") (class "Default")
      (node (ref "C10") (pin "2") (pinfunction "2_2") (pintype "passive"))
      (node (ref "C11") (pin "2") (pinfunction "2_2") (pintype "passive"))
      (node (ref "C12") (pin "2") (pinfunction "2_2") (pintype "passive"))
      (node (ref "C9") (pin "2") (pinfunction "2_2") (pintype "passive"))
      (node (ref "D3") (pin "ANODE") (pinfunction "ANODE_ANODE") (pintype "bidirectional"))
      (node (ref "D4") (pin "ANODE") (pinfunction "ANODE_ANODE") (pintype "bidirectional"))
      (node (ref "D6") (pin "ANODE") (pinfunction "ANODE_ANODE") (pintype "bidirectional"))
      (node (ref "D7") (pin "ANODE") (pinfunction "ANODE_ANODE") (pintype "bidirectional"))
    )
    (net (code "43") (name "Net-(D1-PadA)") (class "Default")
      (node (ref "D1") (pin "A") (pinfunction "A_A") (pintype "passive"))
      (node (ref "R11") (pin "1") (pinfunction "1_1") (pintype "passive"))
    )
    (net (code "44") (name "Net-(D2-B)") (class "Default")
      (node (ref "D2") (pin "3") (pinfunction "B_3") (pintype "output"))
      (node (ref "R9") (pin "1") (pinfunction "1_1") (pintype "passive"))
    )
    (net (code "45") (name "Net-(D2-G)") (class "Default")
      (node (ref "D2") (pin "4") (pinfunction "G_4") (pintype "output"))
      (node (ref "R8") (pin "1") (pinfunction "1_1") (pintype "passive"))
    )
    (net (code "46") (name "Net-(D2-R)") (class "Default")
      (node (ref "D2") (pin "2") (pinfunction "R_2") (pintype "output"))
      (node (ref "R7") (pin "1") (pinfunction "1_1") (pintype "passive"))
    )
    (net (code "47") (name "Net-(D5-ANODE)") (class "Default")
      (node (ref "D5") (pin "A") (pinfunction "ANODE_A") (pintype "bidirectional"))
      (node (ref "R10") (pin "1") (pinfunction "1_1") (pintype "passive"))
    )
    (net (code "48") (name "Net-(D5-CATHODE)") (class "Default")
      (node (ref "D5") (pin "C") (pinfunction "CATHODE_C") (pintype "bidirectional"))
      (node (ref "U7") (pin "4") (pinfunction "TIMEPULSE_4") (pintype "bidirectional"))
    )
    (net (code "49") (name "Net-(IC1A-EN)") (class "Default")
      (node (ref "C28") (pin "1") (pinfunction "1_1") (pintype "passive"))
      (node (ref "IC1") (pin "6") (pinfunction "EN_6") (pintype "input"))
      (node (ref "IC1") (pin "7") (pinfunction "PS/SYNC_7") (pintype "input"))
      (node (ref "IC1") (pin "8") (pinfunction "VINA_8") (pintype "input"))
      (node (ref "R5") (pin "1") (pinfunction "1_1") (pintype "passive"))
    )
    (net (code "50") (name "Net-(IC1A-FB)") (class "Default")
      (node (ref "IC1") (pin "10") (pinfunction "FB_10") (pintype "input"))
      (node (ref "R32") (pin "2") (pinfunction "2_2") (pintype "passive"))
      (node (ref "R36") (pin "1") (pinfunction "1_1") (pintype "passive"))
    )
    (net (code "51") (name "Net-(IC1A-L1)") (class "Default")
      (node (ref "IC1") (pin "4") (pinfunction "L1_4") (pintype "passive"))
      (node (ref "L3") (pin "1") (pinfunction "1_1") (pintype "passive"))
    )
    (net (code "52") (name "Net-(IC1A-L2)") (class "Default")
      (node (ref "IC1") (pin "2") (pinfunction "L2_2") (pintype "passive"))
      (node (ref "L3") (pin "2") (pinfunction "2_2") (pintype "passive"))
    )
    (net (code "53") (name "Net-(J1-VCC)") (class "Default")
      (node (ref "C41") (pin "1") (pinfunction "1_1") (pintype "passive"))
      (node (ref "J1") (pin "4") (pinfunction "VCC_4") (pintype "bidirectional"))
      (node (ref "R18") (pin "2") (pinfunction "2_2") (pintype "passive"))
      (node (ref "R19") (pin "2") (pinfunction "2_2") (pintype "passive"))
      (node (ref "R20") (pin "2") (pinfunction "2_2") (pintype "passive"))
      (node (ref "R28") (pin "2") (pinfunction "2_2") (pintype "passive"))
      (node (ref "U10") (pin "1") (pinfunction "VLOAD_1") (pintype "bidirectional"))
      (node (ref "U10") (pin "2") (pinfunction "VLOAD_2") (pintype "bidirectional"))
    )
    (net (code "54") (name "Net-(J2-D+)") (class "Default")
      (node (ref "C8") (pin "1") (pinfunction "1_1") (pintype "passive"))
      (node (ref "J2") (pin "3") (pinfunction "D+_3") (pintype "bidirectional"))
      (node (ref "R2") (pin "1") (pinfunction "1_1") (pintype "passive"))
    )
    (net (code "55") (name "Net-(J2-D-)") (class "Default")
      (node (ref "C7") (pin "1") (pinfunction "1_1") (pintype "passive"))
      (node (ref "J2") (pin "2") (pinfunction "D-_2") (pintype "bidirectional"))
      (node (ref "R1") (pin "1") (pinfunction "1_1") (pintype "passive"))
    )
    (net (code "56") (name "Net-(J8-ANT)") (class "Default")
      (node (ref "C5") (pin "2") (pinfunction "2_2") (pintype "passive"))
      (node (ref "J8") (pin "SIG") (pinfunction "ANT_SIG") (pintype "bidirectional"))
    )
    (net (code "57") (name "Net-(L2-Pad2)") (class "Default")
      (node (ref "L2") (pin "2") (pinfunction "2_2") (pintype "passive"))
      (node (ref "L4") (pin "1") (pinfunction "1_1") (pintype "passive"))
    )
    (net (code "58") (name "Net-(LED1-ANODE)") (class "Default")
      (node (ref "LED1") (pin "A") (pinfunction "ANODE_A") (pintype "bidirectional"))
      (node (ref "R12") (pin "1") (pinfunction "1_1") (pintype "passive"))
    )
    (net (code "59") (name "Net-(LED1-CATHODE)") (class "Default")
      (node (ref "LED1") (pin "C") (pinfunction "CATHODE_C") (pintype "bidirectional"))
      (node (ref "Q3") (pin "3") (pinfunction "D_3") (pintype "passive"))
    )
    (net (code "60") (name "Net-(Q1-D)") (class "Default")
      (node (ref "Q1") (pin "3") (pinfunction "D_3") (pintype "passive"))
      (node (ref "R29") (pin "1") (pinfunction "1_1") (pintype "passive"))
      (node (ref "U12") (pin "15") (pinfunction "PWR_ON_15") (pintype "bidirectional"))
    )
    (net (code "61") (name "Net-(Q2-D)") (class "Default")
      (node (ref "Q2") (pin "3") (pinfunction "D_3") (pintype "passive"))
      (node (ref "U12") (pin "18") (pinfunction "RESET_N_18") (pintype "bidirectional"))
    )
    (net (code "62") (name "Net-(Q4-G)") (class "Default")
      (node (ref "Q4") (pin "1") (pinfunction "G_1") (pintype "passive"))
      (node (ref "R6") (pin "1") (pinfunction "1_1") (pintype "passive"))
    )
    (net (code "63") (name "Net-(U1-AF)") (class "Default")
      (node (ref "C6") (pin "1") (pinfunction "1_1") (pintype "passive"))
      (node (ref "U1") (pin "14") (pinfunction "AF_14") (pintype "bidirectional"))
    )
    (net (code "64") (name "Net-(U1-VBAT)") (class "Default")
      (node (ref "B1") (pin "+") (pinfunction "+_+") (pintype "bidirectional"))
      (node (ref "R17") (pin "1") (pinfunction "1_1") (pintype "passive"))
      (node (ref "U1") (pin "5") (pinfunction "VBAT_5") (pintype "bidirectional"))
    )
    (net (code "65") (name "Net-(U1-XI)") (class "Default")
      (node (ref "U1") (pin "16") (pinfunction "XI_16") (pintype "bidirectional"))
      (node (ref "X1") (pin "1") (pinfunction "1_1") (pintype "bidirectional"))
    )
    (net (code "66") (name "Net-(U1-XO)") (class "Default")
      (node (ref "U1") (pin "15") (pinfunction "XO_15") (pintype "bidirectional"))
      (node (ref "X1") (pin "2") (pinfunction "2_2") (pintype "bidirectional"))
    )
    (net (code "67") (name "Net-(U2-AI)") (class "Default")
      (node (ref "L1") (pin "1") (pinfunction "1_1") (pintype "passive"))
      (node (ref "U2") (pin "5") (pinfunction "AI_5") (pintype "input"))
    )
    (net (code "68") (name "Net-(U2-AO)") (class "Default")
      (node (ref "U2") (pin "3") (pinfunction "AO_3") (pintype "output"))
      (node (ref "U4") (pin "1") (pinfunction "INPUT_1") (pintype "input"))
    )
    (net (code "69") (name "Net-(U3-RXD)") (class "Default")
      (node (ref "R4") (pin "1") (pinfunction "1_1") (pintype "passive"))
      (node (ref "U3") (pin "10") (pinfunction "RXD_10") (pintype "bidirectional"))
    )
    (net (code "70") (name "Net-(U3-TXD)") (class "Default")
      (node (ref "R3") (pin "1") (pinfunction "1_1") (pintype "passive"))
      (node (ref "U3") (pin "7") (pinfunction "TXD_7") (pintype "bidirectional"))
    )
    (net (code "71") (name "Net-(U3-USBDM)") (class "Default")
      (node (ref "R1") (pin "2") (pinfunction "2_2") (pintype "passive"))
      (node (ref "U3") (pin "1") (pinfunction "USBDM_1") (pintype "bidirectional"))
    )
    (net (code "72") (name "Net-(U3-USBDP)") (class "Default")
      (node (ref "R2") (pin "2") (pinfunction "2_2") (pintype "passive"))
      (node (ref "U3") (pin "12") (pinfunction "USBDP_12") (pintype "bidirectional"))
    )
    (net (code "73") (name "Net-(U3-VCC)") (class "Default")
      (node (ref "C18") (pin "1") (pinfunction "1_1") (pintype "passive"))
      (node (ref "FB1") (pin "P$1") (pinfunction "P$1_P$1") (pintype "bidirectional"))
      (node (ref "U3") (pin "4") (pinfunction "VCC_4") (pintype "bidirectional"))
    )
    (net (code "74") (name "Net-(U4-OUTPUT)") (class "Default")
      (node (ref "U4") (pin "4") (pinfunction "OUTPUT_4") (pintype "bidirectional"))
      (node (ref "U7") (pin "11") (pinfunction "RF_IN_11") (pintype "bidirectional"))
    )
    (net (code "75") (name "Net-(U5-BP)") (class "Default")
      (node (ref "C19") (pin "1") (pinfunction "1_1") (pintype "passive"))
      (node (ref "U5") (pin "4") (pinfunction "BP_4") (pintype "bidirectional"))
    )
    (net (code "76") (name "Net-(U6-PROG)") (class "Default")
      (node (ref "R13") (pin "2") (pinfunction "2_2") (pintype "passive"))
      (node (ref "U6") (pin "8") (pinfunction "PROG_8") (pintype "bidirectional"))
    )
    (net (code "77") (name "Net-(U6-STAT)") (class "Default")
      (node (ref "D1") (pin "C") (pinfunction "C_C") (pintype "passive"))
      (node (ref "U6") (pin "5") (pinfunction "STAT_5") (pintype "bidirectional"))
    )
    (net (code "78") (name "Net-(U7-RXD)") (class "Default")
      (node (ref "L6") (pin "1") (pinfunction "1_1") (pintype "passive"))
      (node (ref "U7") (pin "3") (pinfunction "RXD_3") (pintype "bidirectional"))
    )
    (net (code "79") (name "Net-(U7-TXD)") (class "Default")
      (node (ref "L5") (pin "1") (pinfunction "1_1") (pintype "passive"))
      (node (ref "U7") (pin "2") (pinfunction "TXD_2") (pintype "bidirectional"))
    )
    (net (code "80") (name "Net-(U8-SRT)") (class "Default")
      (node (ref "C31") (pin "1") (pinfunction "1_1") (pintype "passive"))
      (node (ref "U8") (pin "3") (pinfunction "SRT_3") (pintype "bidirectional"))
    )
    (net (code "81") (name "Net-(U8-SWT)") (class "Default")
      (node (ref "C35") (pin "1") (pinfunction "1_1") (pintype "passive"))
      (node (ref "U8") (pin "2") (pinfunction "SWT_2") (pintype "bidirectional"))
    )
    (net (code "82") (name "Net-(U8-~{MR})") (class "Default")
      (node (ref "R33") (pin "1") (pinfunction "1_1") (pintype "passive"))
      (node (ref "R34") (pin "2") (pinfunction "2_2") (pintype "passive"))
      (node (ref "R35") (pin "2") (pinfunction "2_2") (pintype "passive"))
      (node (ref "U8") (pin "1") (pinfunction "~{MR}_1") (pintype "bidirectional"))
    )
    (net (code "83") (name "Net-(U9-DCC)") (class "Default")
      (node (ref "L4") (pin "2") (pinfunction "2_2") (pintype "passive"))
      (node (ref "U9") (pin "B3") (pinfunction "DCC_B3") (pintype "bidirectional"))
    )
    (net (code "84") (name "Net-(U9-DEC1)") (class "Default")
      (node (ref "C25") (pin "1") (pinfunction "1_1") (pintype "passive"))
      (node (ref "U9") (pin "C1") (pinfunction "DEC1_C1") (pintype "bidirectional"))
    )
    (net (code "85") (name "Net-(U9-DEC3)") (class "Default")
      (node (ref "C14") (pin "1") (pinfunction "1_1") (pintype "passive"))
      (node (ref "U9") (pin "D23") (pinfunction "DEC3_D23") (pintype "bidirectional"))
    )
    (net (code "86") (name "Net-(U9-DEC4)") (class "Default")
      (node (ref "C21") (pin "1") (pinfunction "1_1") (pintype "passive"))
      (node (ref "C34") (pin "1") (pinfunction "1_1") (pintype "passive"))
      (node (ref "L2") (pin "1") (pinfunction "1_1") (pintype "passive"))
      (node (ref "U9") (pin "B5") (pinfunction "DEC4_B5") (pintype "bidirectional"))
      (node (ref "U9") (pin "E24") (pinfunction "DEC6_E24") (pintype "bidirectional"))
    )
    (net (code "87") (name "Net-(U9-DEC5)") (class "Default")
      (node (ref "C15") (pin "1") (pinfunction "1_1") (pintype "passive"))
      (node (ref "U9") (pin "N24") (pinfunction "DEC5_N24") (pintype "bidirectional"))
    )
    (net (code "88") (name "Net-(U9-XC1)") (class "Default")
      (node (ref "C1") (pin "2") (pinfunction "2_2") (pintype "passive"))
      (node (ref "U9") (pin "B24") (pinfunction "XC1_B24") (pintype "bidirectional"))
      (node (ref "X4") (pin "3") (pinfunction "2_3") (pintype "bidirectional"))
    )
    (net (code "89") (name "Net-(U9-XC2)") (class "Default")
      (node (ref "C2") (pin "2") (pinfunction "2_2") (pintype "passive"))
      (node (ref "U9") (pin "A23") (pinfunction "XC2_A23") (pintype "bidirectional"))
      (node (ref "X4") (pin "1") (pinfunction "1_1") (pintype "bidirectional"))
    )
    (net (code "90") (name "Net-(U12-ANT)") (class "Default")
      (node (ref "C5") (pin "1") (pinfunction "1_1") (pintype "passive"))
      (node (ref "U12") (pin "56") (pinfunction "ANT_56") (pintype "bidirectional"))
    )
    (net (code "91") (name "Net-(U12-CTS)") (class "Default")
      (node (ref "U12") (pin "11") (pinfunction "CTS_11") (pintype "bidirectional"))
      (node (ref "U13") (pin "3") (pinfunction "A2_3") (pintype "bidirectional"))
    )
    (net (code "92") (name "Net-(U12-RTS)") (class "Default")
      (node (ref "U12") (pin "10") (pinfunction "RTS_10") (pintype "bidirectional"))
      (node (ref "U13") (pin "2") (pinfunction "A1_2") (pintype "bidirectional"))
    )
    (net (code "93") (name "Net-(U12-RXD)") (class "Default")
      (node (ref "U12") (pin "13") (pinfunction "RXD_13") (pintype "bidirectional"))
      (node (ref "U13") (pin "5") (pinfunction "A4_5") (pintype "bidirectional"))
    )
    (net (code "94") (name "Net-(U12-TXD)") (class "Default")
      (node (ref "U12") (pin "12") (pinfunction "TXD_12") (pintype "bidirectional"))
      (node (ref "U13") (pin "4") (pinfunction "A3_4") (pintype "bidirectional"))
    )
    (net (code "95") (name "Net-(U12-V_BCKP)") (class "Default")
      (node (ref "C46") (pin "1") (pinfunction "1_1") (pintype "passive"))
      (node (ref "R29") (pin "2") (pinfunction "2_2") (pintype "passive"))
      (node (ref "U12") (pin "2") (pinfunction "V_BCKP_2") (pintype "bidirectional"))
    )
    (net (code "96") (name "Net-(U13-OE)") (class "Default")
      (node (ref "R25") (pin "1") (pinfunction "1_1") (pintype "passive"))
      (node (ref "U13") (pin "12") (pinfunction "OE_12") (pintype "bidirectional"))
    )
    (net (code "97") (name "RST1") (class "Default")
      (node (ref "J3") (pin "C2") (pinfunction "C2(RST)_C2") (pintype "bidirectional"))
      (node (ref "U20") (pin "2") (pinfunction "NO1_2") (pintype "passive"))
    )
    (net (code "98") (name "RST2") (class "Default")
      (node (ref "J4") (pin "C2") (pinfunction "C2(RST)_C2") (pintype "bidirectional"))
      (node (ref "U20") (pin "9") (pinfunction "NO2_9") (pintype "passive"))
    )
    (net (code "99") (name "RST3") (class "Default")
      (node (ref "J5") (pin "C2") (pinfunction "C2(RST)_C2") (pintype "bidirectional"))
      (node (ref "U20") (pin "4") (pinfunction "NO3_4") (pintype "passive"))
    )
    (net (code "100") (name "RST4") (class "Default")
      (node (ref "J6") (pin "C2") (pinfunction "C2(RST)_C2") (pintype "bidirectional"))
      (node (ref "U20") (pin "7") (pinfunction "NO4_7") (pintype "passive"))
    )
    (net (code "101") (name "RST_SIM") (class "Default")
      (node (ref "C10") (pin "1") (pinfunction "1_1") (pintype "passive"))
      (node (ref "D6") (pin "CATHODE") (pinfunction "CATHODE_CATHODE") (pintype "bidirectional"))
      (node (ref "U12") (pin "40") (pinfunction "SIM_RST_40") (pintype "bidirectional"))
      (node (ref "U20") (pin "8") (pinfunction "COM_8") (pintype "passive"))
    )
    (net (code "102") (name "SD_EN") (class "Default")
      (node (ref "R27") (pin "1") (pinfunction "1_1") (pintype "passive"))
      (node (ref "TP6") (pin "P$1") (pinfunction "TESTPOINT_P$1") (pintype "bidirectional"))
      (node (ref "U10") (pin "3") (pinfunction "EN_3") (pintype "bidirectional"))
      (node (ref "U9") (pin "AC9") (pinfunction "P0.14_AC9") (pintype "bidirectional"))
    )
    (net (code "103") (name "UART_RX") (class "Default")
      (node (ref "R3") (pin "2") (pinfunction "2_2") (pintype "passive"))
      (node (ref "TP24") (pin "P$1") (pinfunction "TESTPOINT_P$1") (pintype "bidirectional"))
      (node (ref "U9") (pin "A16") (pinfunction "P1.13_A16") (pintype "bidirectional"))
    )
    (net (code "104") (name "UART_TX") (class "Default")
      (node (ref "R4") (pin "2") (pinfunction "2_2") (pintype "passive"))
      (node (ref "TP25") (pin "P$1") (pinfunction "TESTPOINT_P$1") (pintype "bidirectional"))
      (node (ref "U9") (pin "A14") (pinfunction "P1.15_A14") (pintype "bidirectional"))
    )
    (net (code "105") (name "VCC") (class "Default")
      (node (ref "C24") (pin "1") (pinfunction "1_1") (pintype "passive"))
      (node (ref "C26") (pin "1") (pinfunction "1_1") (pintype "passive"))
      (node (ref "C27") (pin "1") (pinfunction "1_1") (pintype "passive"))
      (node (ref "C29") (pin "1") (pinfunction "1_1") (pintype "passive"))
      (node (ref "C32") (pin "1") (pinfunction "1_1") (pintype "passive"))
      (node (ref "C33") (pin "1") (pinfunction "1_1") (pintype "passive"))
      (node (ref "C39") (pin "1") (pinfunction "1_1") (pintype "passive"))
      (node (ref "C40") (pin "1") (pinfunction "1_1") (pintype "passive"))
      (node (ref "D2") (pin "1") (pinfunction "VDD_1") (pintype "bidirectional"))
      (node (ref "J7") (pin "1") (pinfunction "VCC_1") (pintype "bidirectional"))
      (node (ref "R14") (pin "1") (pinfunction "1_1") (pintype "passive"))
      (node (ref "R15") (pin "1") (pinfunction "1_1") (pintype "passive"))
      (node (ref "R25") (pin "2") (pinfunction "2_2") (pintype "passive"))
      (node (ref "TP27") (pin "P$1") (pinfunction "TESTPOINT_P$1") (pintype "bidirectional"))
      (node (ref "TP31") (pin "TP") (pinfunction "TP_TP") (pintype "input"))
      (node (ref "U1") (pin "13") (pinfunction "VCC_13") (pintype "bidirectional"))
      (node (ref "U10") (pin "5") (pinfunction "VSUPP_5") (pintype "bidirectional"))
      (node (ref "U10") (pin "6") (pinfunction "VSUPP_6") (pintype "bidirectional"))
      (node (ref "U11") (pin "5") (pinfunction "VSUPP_5") (pintype "bidirectional"))
      (node (ref "U11") (pin "6") (pinfunction "VSUPP_6") (pintype "bidirectional"))
      (node (ref "U13") (pin "11") (pinfunction "VCC_B_11") (pintype "bidirectional"))
      (node (ref "U3") (pin "9") (pinfunction "VCCIO_9") (pintype "bidirectional"))
      (node (ref "U5") (pin "5") (pinfunction "OUT_5") (pintype "bidirectional"))
      (node (ref "U9") (pin "A22") (pinfunction "VDD_A22") (pintype "bidirectional"))
      (node (ref "U9") (pin "AD14") (pinfunction "VDD_AD14") (pintype "bidirectional"))
      (node (ref "U9") (pin "AD23") (pinfunction "VDD_AD23") (pintype "bidirectional"))
      (node (ref "U9") (pin "B1") (pinfunction "VDD_B1") (pintype "bidirectional"))
      (node (ref "U9") (pin "W1") (pinfunction "VDD_W1") (pintype "bidirectional"))
      (node (ref "U9") (pin "Y2") (pinfunction "VDDH_Y2") (pintype "bidirectional"))
    )
    (net (code "106") (name "VCC1") (class "Default")
      (node (ref "J3") (pin "C1") (pinfunction "C1(VCC)_C1") (pintype "bidirectional"))
      (node (ref "R24") (pin "1") (pinfunction "1_1") (pintype "passive"))
      (node (ref "U15") (pin "2") (pinfunction "NO1_2") (pintype "passive"))
    )
    (net (code "107") (name "VCC2") (class "Default")
      (node (ref "J4") (pin "C1") (pinfunction "C1(VCC)_C1") (pintype "bidirectional"))
      (node (ref "R23") (pin "1") (pinfunction "1_1") (pintype "passive"))
      (node (ref "U15") (pin "9") (pinfunction "NO2_9") (pintype "passive"))
    )
    (net (code "108") (name "VCC3") (class "Default")
      (node (ref "J5") (pin "C1") (pinfunction "C1(VCC)_C1") (pintype "bidirectional"))
      (node (ref "R22") (pin "1") (pinfunction "1_1") (pintype "passive"))
      (node (ref "U15") (pin "4") (pinfunction "NO3_4") (pintype "passive"))
    )
    (net (code "109") (name "VCC4") (class "Default")
      (node (ref "J6") (pin "C1") (pinfunction "C1(VCC)_C1") (pintype "bidirectional"))
      (node (ref "R21") (pin "1") (pinfunction "1_1") (pintype "passive"))
      (node (ref "U15") (pin "7") (pinfunction "NO4_7") (pintype "passive"))
    )
    (net (code "110") (name "VCCA") (class "Default")
      (node (ref "C38") (pin "1") (pinfunction "1_1") (pintype "passive"))
      (node (ref "C44") (pin "1") (pinfunction "1_1") (pintype "passive"))
      (node (ref "C45") (pin "1") (pinfunction "1_1") (pintype "passive"))
      (node (ref "IC1") (pin "1") (pinfunction "VOUT_1") (pintype "output"))
      (node (ref "Q4") (pin "2") (pinfunction "S_2") (pintype "passive"))
      (node (ref "R36") (pin "2") (pinfunction "2_2") (pintype "passive"))
      (node (ref "U5") (pin "1") (pinfunction "IN_1") (pintype "bidirectional"))
      (node (ref "U5") (pin "3") (pinfunction "~{SHDN}_3") (pintype "bidirectional"))
    )
    (net (code "111") (name "VCC_RF") (class "Default")
      (node (ref "C16") (pin "2") (pinfunction "2_2") (pintype "passive"))
      (node (ref "U2") (pin "2") (pinfunction "VCC_2") (pintype "power_in"))
      (node (ref "U2") (pin "6") (pinfunction "PON_6") (pintype "input"))
      (node (ref "U7") (pin "14") (pinfunction "VCC_RF_14") (pintype "bidirectional"))
    )
    (net (code "112") (name "VCC_SIM") (class "Default")
      (node (ref "C11") (pin "1") (pinfunction "1_1") (pintype "passive"))
      (node (ref "D3") (pin "CATHODE") (pinfunction "CATHODE_CATHODE") (pintype "bidirectional"))
      (node (ref "U12") (pin "41") (pinfunction "VSIM_41") (pintype "bidirectional"))
      (node (ref "U15") (pin "8") (pinfunction "COM_8") (pintype "passive"))
    )
    (net (code "113") (name "V_GSM_INT") (class "Default")
      (node (ref "U12") (pin "4") (pinfunction "V_INT_4") (pintype "bidirectional"))
      (node (ref "U13") (pin "1") (pinfunction "VCC_A_1") (pintype "bidirectional"))
    )
    (net (code "114") (name "WDI") (class "Default")
      (node (ref "TP3") (pin "P$1") (pinfunction "TESTPOINT_P$1") (pintype "bidirectional"))
      (node (ref "U8") (pin "6") (pinfunction "WDI_6") (pintype "bidirectional"))
      (node (ref "U9") (pin "T2") (pinfunction "P0.11_T2") (pintype "bidirectional"))
    )
    (net (code "115") (name "XL3") (class "Default")
      (node (ref "C4") (pin "2") (pinfunction "2_2") (pintype "passive"))
      (node (ref "U9") (pin "D2") (pinfunction "P0.00/XL1_D2") (pintype "bidirectional"))
      (node (ref "X5") (pin "A") (pinfunction "1_A") (pintype "bidirectional"))
    )
    (net (code "116") (name "XL4") (class "Default")
      (node (ref "C3") (pin "2") (pinfunction "2_2") (pintype "passive"))
      (node (ref "U9") (pin "F2") (pinfunction "P0.01/XL2_F2") (pintype "bidirectional"))
      (node (ref "X5") (pin "B") (pinfunction "2_B") (pintype "bidirectional"))
    )
    (net (code "117") (name "unconnected-(J1-DATA1{slash}RSV-Pad8)") (class "Default")
      (node (ref "J1") (pin "8") (pinfunction "DATA1/RSV_8") (pintype "bidirectional"))
    )
    (net (code "118") (name "unconnected-(J1-DATA2{slash}NC-Pad1)") (class "Default")
      (node (ref "J1") (pin "1") (pinfunction "DATA2/NC_1") (pintype "bidirectional"))
    )
    (net (code "119") (name "unconnected-(J2-ID-Pad4)") (class "Default")
      (node (ref "J2") (pin "4") (pinfunction "ID_4") (pintype "bidirectional"))
    )
    (net (code "120") (name "unconnected-(J3-C6(VPP)-PadC6)") (class "Default")
      (node (ref "J3") (pin "C6") (pinfunction "C6(VPP)_C6") (pintype "bidirectional"))
    )
    (net (code "121") (name "unconnected-(J4-C6(VPP)-PadC6)") (class "Default")
      (node (ref "J4") (pin "C6") (pinfunction "C6(VPP)_C6") (pintype "bidirectional"))
    )
    (net (code "122") (name "unconnected-(J5-C6(VPP)-PadC6)") (class "Default")
      (node (ref "J5") (pin "C6") (pinfunction "C6(VPP)_C6") (pintype "bidirectional"))
    )
    (net (code "123") (name "unconnected-(J6-C6(VPP)-PadC6)") (class "Default")
      (node (ref "J6") (pin "C6") (pinfunction "C6(VPP)_C6") (pintype "bidirectional"))
    )
    (net (code "124") (name "unconnected-(J7-SWO-Pad6)") (class "Default")
      (node (ref "J7") (pin "6") (pinfunction "SWO_6") (pintype "bidirectional"))
    )
    (net (code "125") (name "unconnected-(U1-CLKOUT{slash}~{IRQ3}-Pad8)") (class "Default")
      (node (ref "U1") (pin "8") (pinfunction "CLKOUT/~{IRQ3}_8") (pintype "bidirectional"))
    )
    (net (code "126") (name "unconnected-(U1-WDI-Pad2)") (class "Default")
      (node (ref "U1") (pin "2") (pinfunction "WDI_2") (pintype "bidirectional"))
    )
    (net (code "127") (name "unconnected-(U1-~{IRQ2}-Pad4)") (class "Default")
      (node (ref "U1") (pin "4") (pinfunction "~{IRQ2}_4") (pintype "bidirectional"))
    )
    (net (code "128") (name "unconnected-(U1-~{RST}-Pad1)") (class "Default")
      (node (ref "U1") (pin "1") (pinfunction "~{RST}_1") (pintype "bidirectional"))
    )
    (net (code "129") (name "unconnected-(U3-3V3OUT-Pad3)") (class "Default")
      (node (ref "U3") (pin "3") (pinfunction "3V3OUT_3") (pintype "bidirectional"))
    )
    (net (code "130") (name "unconnected-(U3-CBUS0-Pad6)") (class "Default")
      (node (ref "U3") (pin "6") (pinfunction "CBUS0_6") (pintype "bidirectional"))
    )
    (net (code "131") (name "unconnected-(U3-~{CTS}-Pad11)") (class "Default")
      (node (ref "U3") (pin "11") (pinfunction "~{CTS}_11") (pintype "bidirectional"))
    )
    (net (code "132") (name "unconnected-(U3-~{RESET}-Pad2)") (class "Default")
      (node (ref "U3") (pin "2") (pinfunction "~{RESET}_2") (pintype "bidirectional"))
    )
    (net (code "133") (name "unconnected-(U3-~{RTS}-Pad8)") (class "Default")
      (node (ref "U3") (pin "8") (pinfunction "~{RTS}_8") (pintype "bidirectional"))
    )
    (net (code "134") (name "unconnected-(U6-NC-Pad7)") (class "Default")
      (node (ref "U6") (pin "7") (pinfunction "NC_7") (pintype "no_connect"))
    )
    (net (code "135") (name "unconnected-(U7-EXTINT-Pad5)") (class "Default")
      (node (ref "U7") (pin "5") (pinfunction "EXTINT_5") (pintype "bidirectional"))
    )
    (net (code "136") (name "unconnected-(U7-LNA_EN-Pad13)") (class "Default")
      (node (ref "U7") (pin "13") (pinfunction "LNA_EN_13") (pintype "bidirectional"))
    )
    (net (code "137") (name "unconnected-(U7-SCL-Pad17)") (class "Default")
      (node (ref "U7") (pin "17") (pinfunction "SCL_17") (pintype "bidirectional"))
    )
    (net (code "138") (name "unconnected-(U7-SDA-Pad16)") (class "Default")
      (node (ref "U7") (pin "16") (pinfunction "SDA_16") (pintype "bidirectional"))
    )
    (net (code "139") (name "unconnected-(U7-V_ANT-Pad15)") (class "Default")
      (node (ref "U7") (pin "15") (pinfunction "V_ANT_15") (pintype "bidirectional"))
    )
    (net (code "140") (name "unconnected-(U7-~{RESET}-Pad9)") (class "Default")
      (node (ref "U7") (pin "9") (pinfunction "~{RESET}_9") (pintype "bidirectional"))
    )
    (net (code "141") (name "unconnected-(U7-~{SAFEBOOT}-Pad18)") (class "Default")
      (node (ref "U7") (pin "18") (pinfunction "~{SAFEBOOT}_18") (pintype "bidirectional"))
    )
    (net (code "142") (name "unconnected-(U9-ANT-PadH23)") (class "Default")
      (node (ref "U9") (pin "H23") (pinfunction "ANT_H23") (pintype "bidirectional"))
    )
    (net (code "143") (name "unconnected-(U9-D+-PadAD6)") (class "Default")
      (node (ref "U9") (pin "AD6") (pinfunction "D+_AD6") (pintype "bidirectional"))
    )
    (net (code "144") (name "unconnected-(U9-D--PadAD4)") (class "Default")
      (node (ref "U9") (pin "AD4") (pinfunction "D-_AD4") (pintype "bidirectional"))
    )
    (net (code "145") (name "unconnected-(U9-DCCH-PadAB2)") (class "Default")
      (node (ref "U9") (pin "AB2") (pinfunction "DCCH_AB2") (pintype "bidirectional"))
    )
    (net (code "146") (name "unconnected-(U9-DEC2-PadA18)") (class "Default")
      (node (ref "U9") (pin "A18") (pinfunction "DEC2_A18") (pintype "bidirectional"))
    )
    (net (code "147") (name "unconnected-(U9-DECUSB-PadAC5)") (class "Default")
      (node (ref "U9") (pin "AC5") (pinfunction "DECUSB_AC5") (pintype "bidirectional"))
    )
    (net (code "148") (name "unconnected-(U9-P0.09{slash}NFC1-PadL24)") (class "Default")
      (node (ref "U9") (pin "L24") (pinfunction "P0.09/NFC1_L24") (pintype "bidirectional"))
    )
    (net (code "149") (name "unconnected-(U9-P0.10{slash}NFC2-PadJ24)") (class "Default")
      (node (ref "U9") (pin "J24") (pinfunction "P0.10/NFC2_J24") (pintype "bidirectional"))
    )
    (net (code "150") (name "unconnected-(U9-P0.21-PadAC17)") (class "Default")
      (node (ref "U9") (pin "AC17") (pinfunction "P0.21_AC17") (pintype "bidirectional"))
    )
    (net (code "151") (name "unconnected-(U9-P0.22-PadAD18)") (class "Default")
      (node (ref "U9") (pin "AD18") (pinfunction "P0.22_AD18") (pintype "bidirectional"))
    )
    (net (code "152") (name "unconnected-(U9-P0.23-PadAC19)") (class "Default")
      (node (ref "U9") (pin "AC19") (pinfunction "P0.23_AC19") (pintype "bidirectional"))
    )
    (net (code "153") (name "unconnected-(U9-P1.01-PadY23)") (class "Default")
      (node (ref "U9") (pin "Y23") (pinfunction "P1.01_Y23") (pintype "bidirectional"))
    )
    (net (code "154") (name "unconnected-(U9-P1.02-PadW24)") (class "Default")
      (node (ref "U9") (pin "W24") (pinfunction "P1.02_W24") (pintype "bidirectional"))
    )
    (net (code "155") (name "unconnected-(U9-P1.03-PadV23)") (class "Default")
      (node (ref "U9") (pin "V23") (pinfunction "P1.03_V23") (pintype "bidirectional"))
    )
    (net (code "156") (name "unconnected-(U9-P1.04-PadU24)") (class "Default")
      (node (ref "U9") (pin "U24") (pinfunction "P1.04_U24") (pintype "bidirectional"))
    )
    (net (code "157") (name "unconnected-(U9-P1.05-PadT23)") (class "Default")
      (node (ref "U9") (pin "T23") (pinfunction "P1.05_T23") (pintype "bidirectional"))
    )
    (net (code "158") (name "unconnected-(U9-P1.07-PadP23)") (class "Default")
      (node (ref "U9") (pin "P23") (pinfunction "P1.07_P23") (pintype "bidirectional"))
    )
    (net (code "159") (name "unconnected-(U9-P1.08-PadP2)") (class "Default")
      (node (ref "U9") (pin "P2") (pinfunction "P1.08_P2") (pintype "bidirectional"))
    )
    (net (code "160") (name "unconnected-(U9-P1.10-PadA20)") (class "Default")
      (node (ref "U9") (pin "A20") (pinfunction "P1.10_A20") (pintype "bidirectional"))
    )
    (net (code "161") (name "unconnected-(U9-P1.11-PadB19)") (class "Default")
      (node (ref "U9") (pin "B19") (pinfunction "P1.11_B19") (pintype "bidirectional"))
    )
    (net (code "162") (name "unconnected-(U9-P1.12-PadB17)") (class "Default")
      (node (ref "U9") (pin "B17") (pinfunction "P1.12_B17") (pintype "bidirectional"))
    )
    (net (code "163") (name "unconnected-(U9-P1.14-PadB15)") (class "Default")
      (node (ref "U9") (pin "B15") (pinfunction "P1.14_B15") (pintype "bidirectional"))
    )
    (net (code "164") (name "unconnected-(U12-ANT_DET-Pad62)") (class "Default")
      (node (ref "U12") (pin "62") (pinfunction "ANT_DET_62") (pintype "bidirectional"))
    )
    (net (code "165") (name "unconnected-(U12-DCD-Pad8)") (class "Default")
      (node (ref "U12") (pin "8") (pinfunction "DCD_8") (pintype "bidirectional"))
    )
    (net (code "166") (name "unconnected-(U12-DSR-Pad6)") (class "Default")
      (node (ref "U12") (pin "6") (pinfunction "DSR_6") (pintype "bidirectional"))
    )
    (net (code "167") (name "unconnected-(U12-GPIO2-Pad23)") (class "Default")
      (node (ref "U12") (pin "23") (pinfunction "GPIO2_23") (pintype "bidirectional"))
    )
    (net (code "168") (name "unconnected-(U12-GPIO3-Pad24)") (class "Default")
      (node (ref "U12") (pin "24") (pinfunction "GPIO3_24") (pintype "bidirectional"))
    )
    (net (code "169") (name "unconnected-(U12-GPIO4-Pad25)") (class "Default")
      (node (ref "U12") (pin "25") (pinfunction "GPIO4_25") (pintype "bidirectional"))
    )
    (net (code "170") (name "unconnected-(U12-I2S_CLK-Pad36)") (class "Default")
      (node (ref "U12") (pin "36") (pinfunction "I2S_CLK_36") (pintype "bidirectional"))
    )
    (net (code "171") (name "unconnected-(U12-I2S_RXD-Pad37)") (class "Default")
      (node (ref "U12") (pin "37") (pinfunction "I2S_RXD_37") (pintype "bidirectional"))
    )
    (net (code "172") (name "unconnected-(U12-I2S_TXD-Pad35)") (class "Default")
      (node (ref "U12") (pin "35") (pinfunction "I2S_TXD_35") (pintype "bidirectional"))
    )
    (net (code "173") (name "unconnected-(U12-I2S_WA-Pad34)") (class "Default")
      (node (ref "U12") (pin "34") (pinfunction "I2S_WA_34") (pintype "bidirectional"))
    )
    (net (code "174") (name "unconnected-(U12-MIC_BIAS-Pad46)") (class "Default")
      (node (ref "U12") (pin "46") (pinfunction "MIC_BIAS_46") (pintype "bidirectional"))
    )
    (net (code "175") (name "unconnected-(U12-MIC_GND-Pad47)") (class "Default")
      (node (ref "U12") (pin "47") (pinfunction "MIC_GND_47") (pintype "bidirectional"))
    )
    (net (code "176") (name "unconnected-(U12-MIC_N-Pad48)") (class "Default")
      (node (ref "U12") (pin "48") (pinfunction "MIC_N_48") (pintype "bidirectional"))
    )
    (net (code "177") (name "unconnected-(U12-MIC_P-Pad49)") (class "Default")
      (node (ref "U12") (pin "49") (pinfunction "MIC_P_49") (pintype "bidirectional"))
    )
    (net (code "178") (name "unconnected-(U12-RI-Pad7)") (class "Default")
      (node (ref "U12") (pin "7") (pinfunction "RI_7") (pintype "bidirectional"))
    )
    (net (code "179") (name "unconnected-(U12-RXD_AUX-Pad28)") (class "Default")
      (node (ref "U12") (pin "28") (pinfunction "RXD_AUX_28") (pintype "bidirectional"))
    )
    (net (code "180") (name "unconnected-(U12-SCL-Pad27)") (class "Default")
      (node (ref "U12") (pin "27") (pinfunction "SCL_27") (pintype "bidirectional"))
    )
    (net (code "181") (name "unconnected-(U12-SDA-Pad26)") (class "Default")
      (node (ref "U12") (pin "26") (pinfunction "SDA_26") (pintype "bidirectional"))
    )
    (net (code "182") (name "unconnected-(U12-SIM_DET-Pad42)") (class "Default")
      (node (ref "U12") (pin "42") (pinfunction "SIM_DET_42") (pintype "bidirectional"))
    )
    (net (code "183") (name "unconnected-(U12-SPK_N-Pad45)") (class "Default")
      (node (ref "U12") (pin "45") (pinfunction "SPK_N_45") (pintype "bidirectional"))
    )
    (net (code "184") (name "unconnected-(U12-SPK_P-Pad44)") (class "Default")
      (node (ref "U12") (pin "44") (pinfunction "SPK_P_44") (pintype "bidirectional"))
    )
    (net (code "185") (name "unconnected-(U12-TXD_AUX-Pad29)") (class "Default")
      (node (ref "U12") (pin "29") (pinfunction "TXD_AUX_29") (pintype "bidirectional"))
    )
    (net (code "186") (name "~{EXTERNAL_RST}") (class "Default")
      (node (ref "R16") (pin "2") (pinfunction "2_2") (pintype "passive"))
      (node (ref "TP12") (pin "P$1") (pinfunction "TESTPOINT_P$1") (pintype "bidirectional"))
      (node (ref "U8") (pin "7") (pinfunction "~{RESET}_7") (pintype "bidirectional"))
      (node (ref "U9") (pin "AD20") (pinfunction "P0.24_AD20") (pintype "bidirectional"))
    )
    (net (code "187") (name "~{NRF_CS_SD}") (class "Default")
      (node (ref "J1") (pin "2") (pinfunction "DATA3-CD/CS_N_2") (pintype "bidirectional"))
      (node (ref "R19") (pin "1") (pinfunction "1_1") (pintype "passive"))
      (node (ref "TP11") (pin "P$1") (pinfunction "TESTPOINT_P$1") (pintype "bidirectional"))
      (node (ref "U9") (pin "AD16") (pinfunction "P0.20_AD16") (pintype "bidirectional"))
    )
    (net (code "188") (name "~{NRF_RST}") (class "Default")
      (node (ref "J7") (pin "3") (pinfunction "~{RESET}_3") (pintype "bidirectional"))
      (node (ref "TP13") (pin "P$1") (pinfunction "TESTPOINT_P$1") (pintype "bidirectional"))
      (node (ref "U9") (pin "AC13") (pinfunction "P0.18_AC13") (pintype "bidirectional"))
    )
    (net (code "189") (name "~{RTC_CS}") (class "Default")
      (node (ref "R15") (pin "2") (pinfunction "2_2") (pintype "passive"))
      (node (ref "R17") (pin "2") (pinfunction "2_2") (pintype "passive"))
      (node (ref "TP4") (pin "P$1") (pinfunction "TESTPOINT_P$1") (pintype "bidirectional"))
      (node (ref "U1") (pin "12") (pinfunction "~{CS}_12") (pintype "bidirectional"))
      (node (ref "U9") (pin "U1") (pinfunction "P0.12_U1") (pintype "bidirectional"))
    )
    (net (code "190") (name "~{RTC_INT1}") (class "Default")
      (node (ref "R14") (pin "2") (pinfunction "2_2") (pintype "passive"))
      (node (ref "TP8") (pin "P$1") (pinfunction "TESTPOINT_P$1") (pintype "bidirectional"))
      (node (ref "U1") (pin "11") (pinfunction "FOUT/~{IRQ1}_11") (pintype "bidirectional"))
      (node (ref "U9") (pin "AC11") (pinfunction "P0.16_AC11") (pintype "bidirectional"))
    )
    (net (code "191") (name "~{SD_DETECT}") (class "Default")
      (node (ref "J1") (pin "A") (pinfunction "A_A") (pintype "bidirectional"))
      (node (ref "R28") (pin "1") (pinfunction "1_1") (pintype "passive"))
      (node (ref "TP21") (pin "P$1") (pinfunction "TESTPOINT_P$1") (pintype "bidirectional"))
      (node (ref "U9") (pin "AD22") (pinfunction "P1.00_AD22") (pintype "bidirectional"))
    )
  )
)
